# WS2812B.net
KiCad netlist of a schematic drawn in Altium Designer
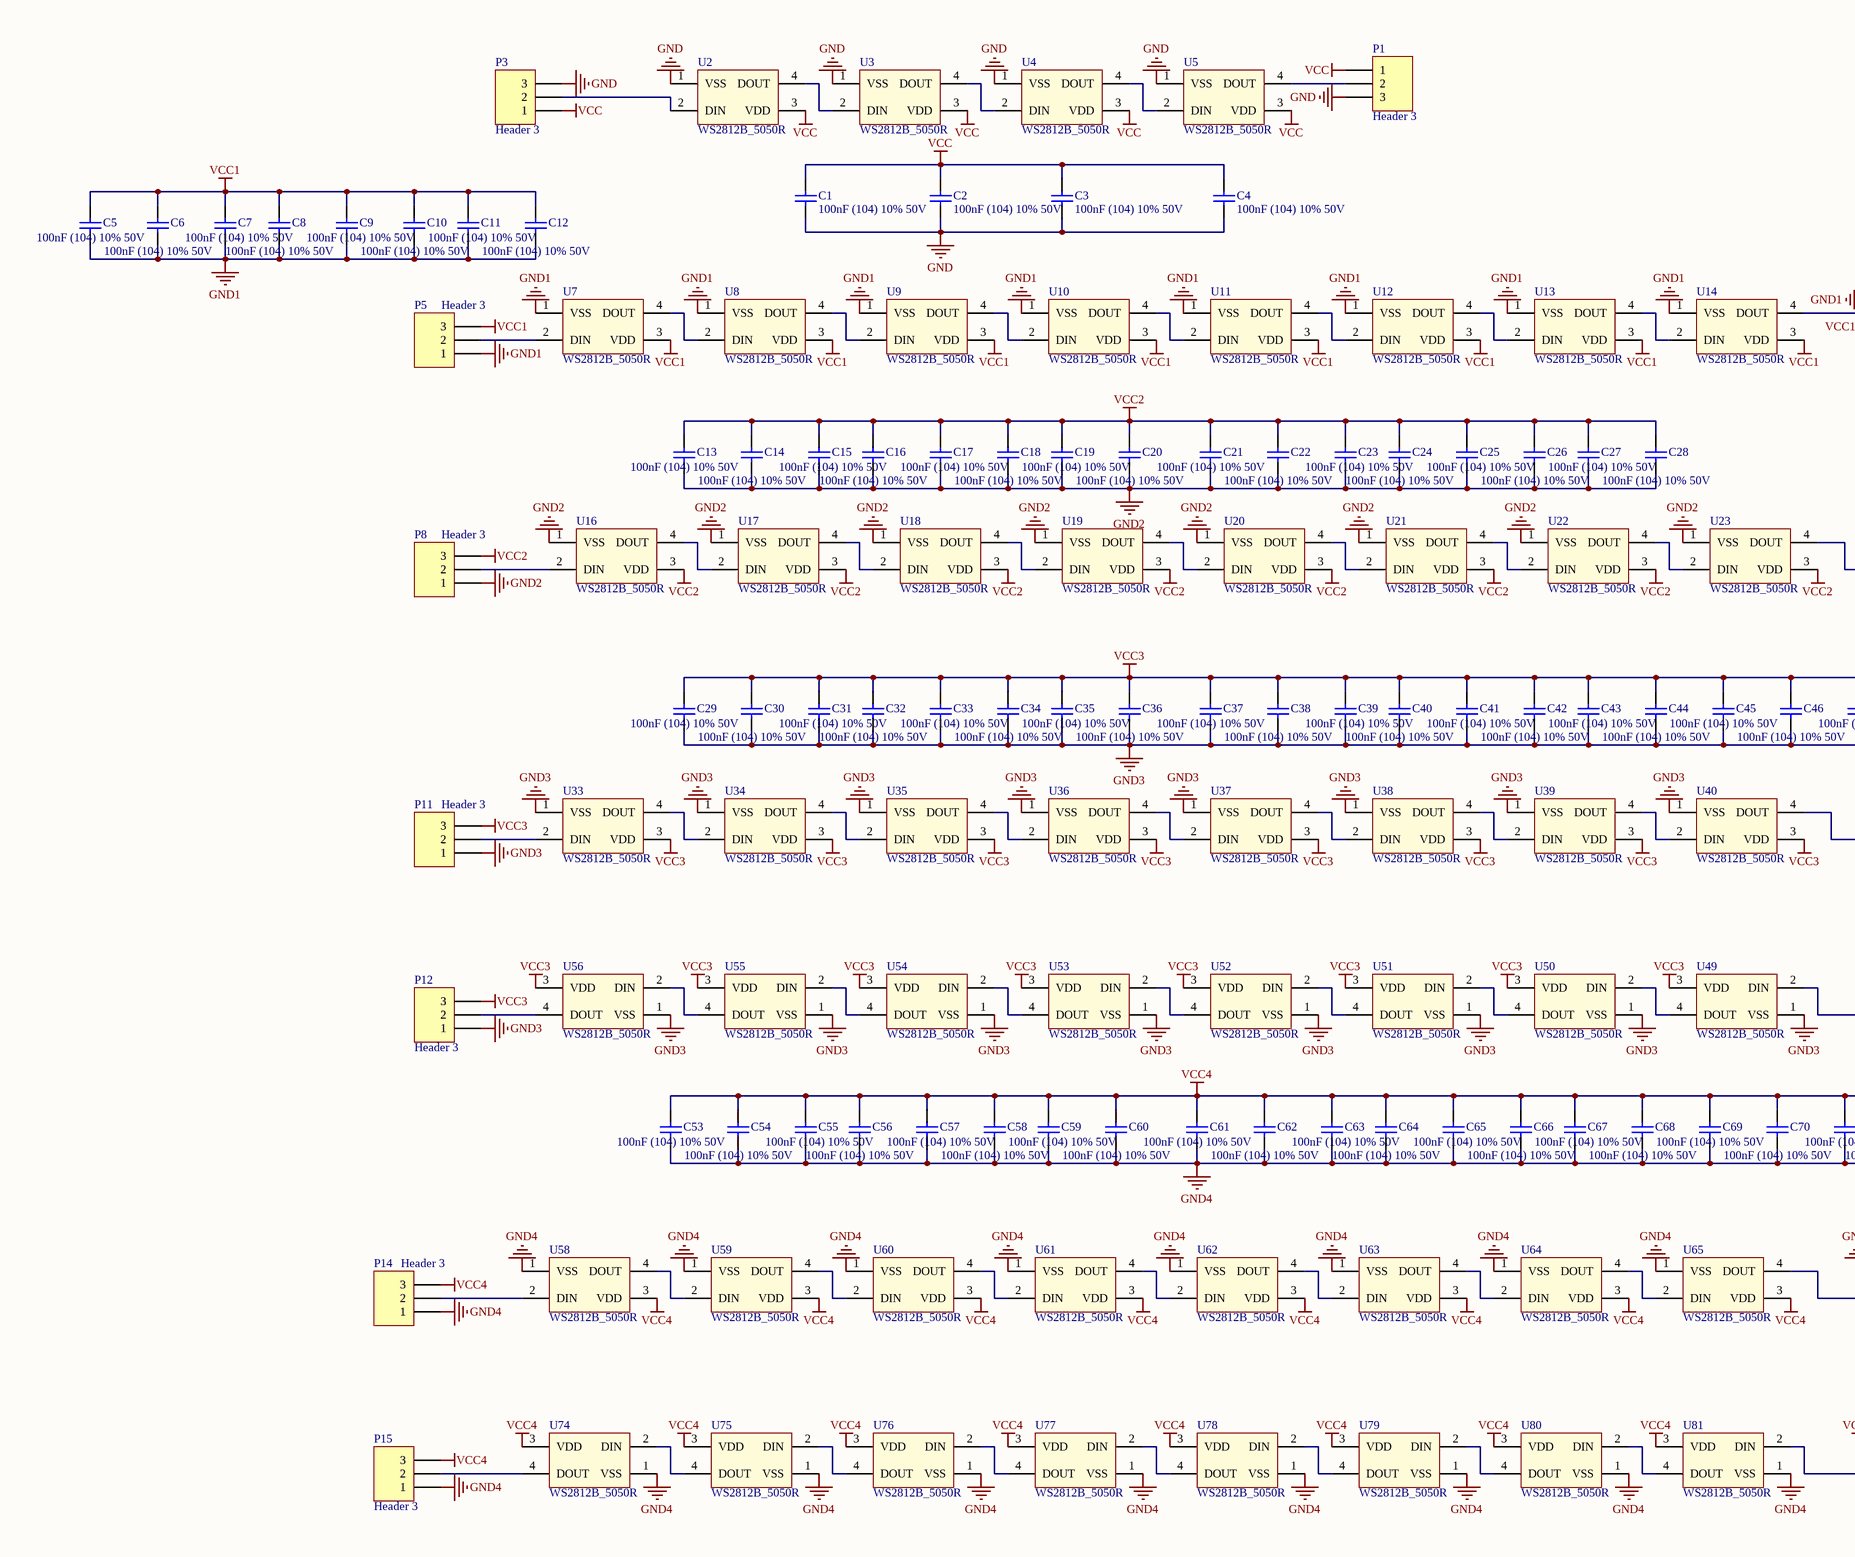
[diagram p0: WS2812B.SchDoc, left]
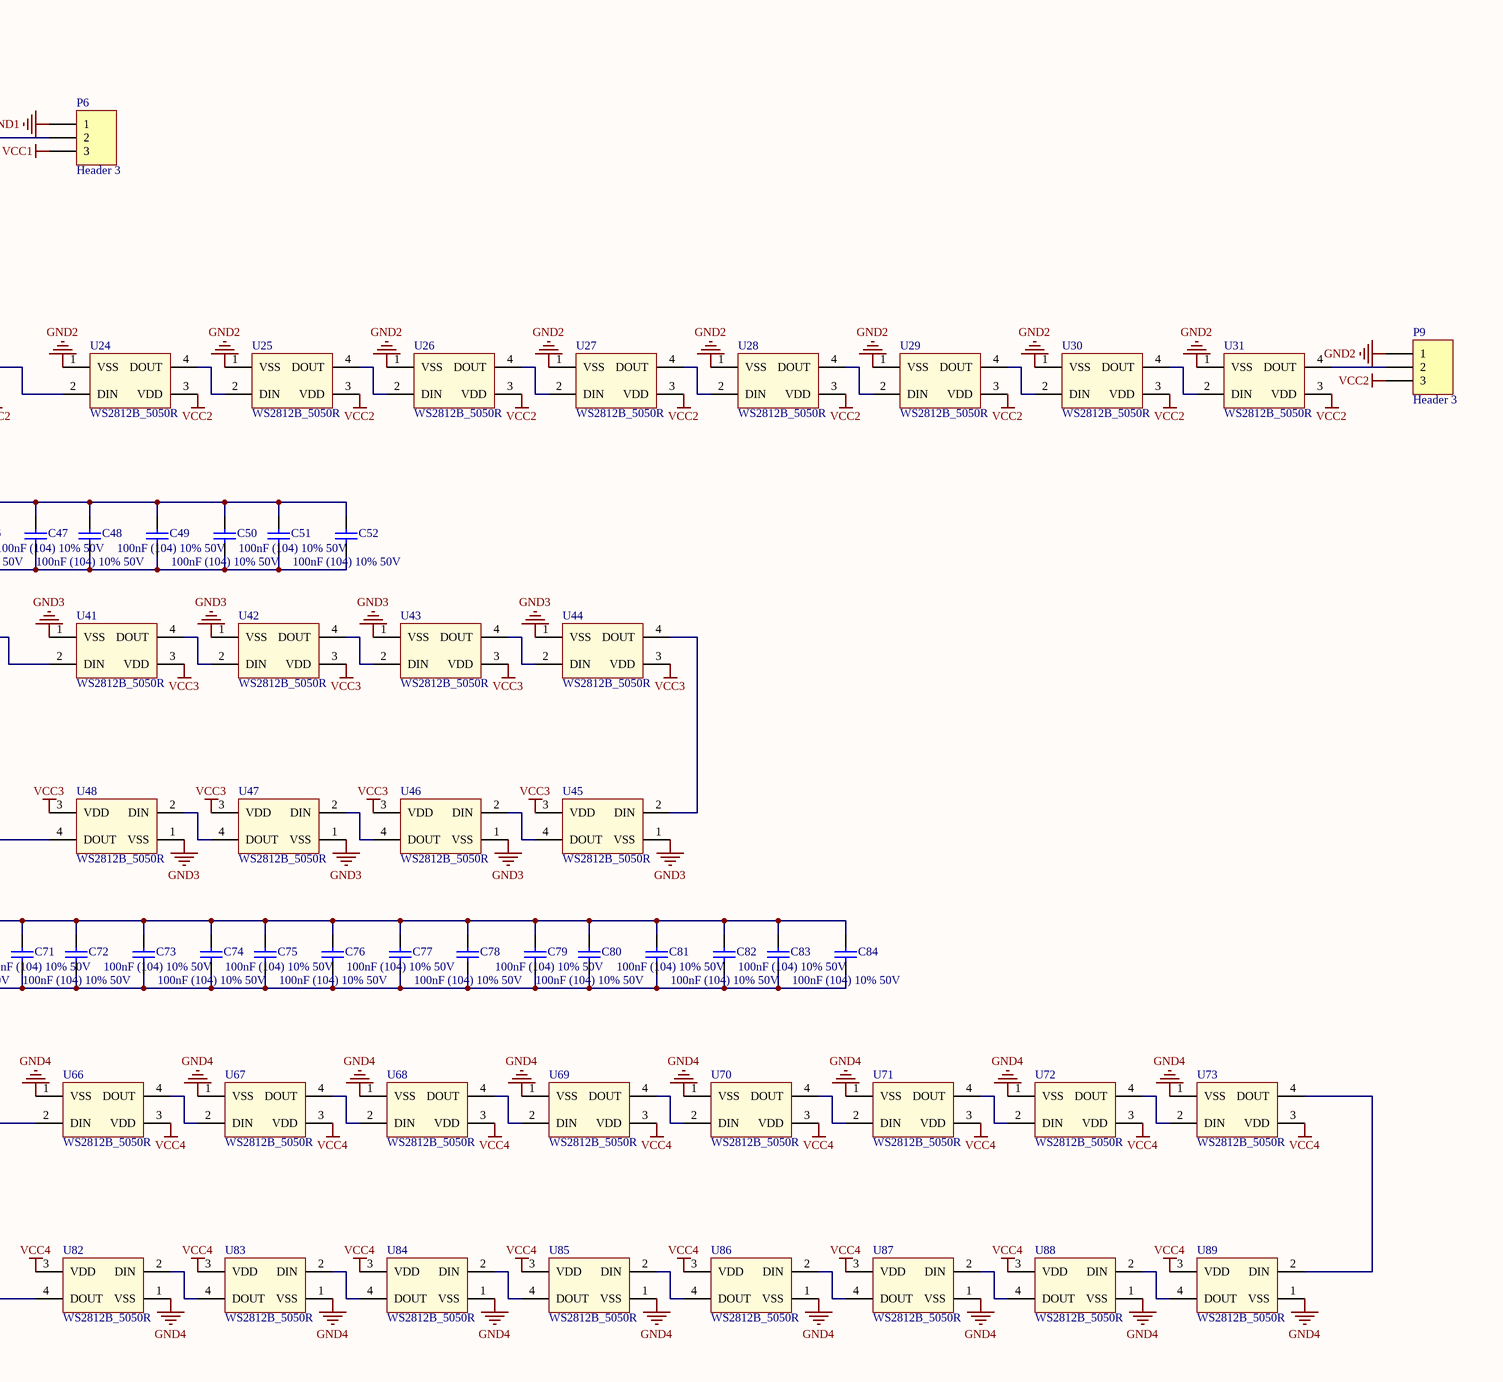
[diagram p1: WS2812B.SchDoc, right]

(export (version "E")
  (design (tool "Eeschema 10.0.6"))
  (components
    (comp (ref "C1")
      (value "100nF (104) 10% 50V")
      (footprint "0603_C")
      (description "贴片电容")
      (libsource (lib "Cap") (part "0603 100nF (104) 10% 50V"))
    )
    (comp (ref "C2")
      (value "100nF (104) 10% 50V")
      (footprint "0603_C")
      (description "贴片电容")
      (libsource (lib "Cap") (part "0603 100nF (104) 10% 50V"))
    )
    (comp (ref "C3")
      (value "100nF (104) 10% 50V")
      (footprint "0603_C")
      (description "贴片电容")
      (libsource (lib "Cap") (part "0603 100nF (104) 10% 50V"))
    )
    (comp (ref "C4")
      (value "100nF (104) 10% 50V")
      (footprint "0603_C")
      (description "贴片电容")
      (libsource (lib "Cap") (part "0603 100nF (104) 10% 50V"))
    )
    (comp (ref "C5")
      (value "100nF (104) 10% 50V")
      (footprint "0603_C")
      (description "贴片电容")
      (libsource (lib "Cap") (part "0603 100nF (104) 10% 50V"))
    )
    (comp (ref "C6")
      (value "100nF (104) 10% 50V")
      (footprint "0603_C")
      (description "贴片电容")
      (libsource (lib "Cap") (part "0603 100nF (104) 10% 50V"))
    )
    (comp (ref "C7")
      (value "100nF (104) 10% 50V")
      (footprint "0603_C")
      (description "贴片电容")
      (libsource (lib "Cap") (part "0603 100nF (104) 10% 50V"))
    )
    (comp (ref "C8")
      (value "100nF (104) 10% 50V")
      (footprint "0603_C")
      (description "贴片电容")
      (libsource (lib "Cap") (part "0603 100nF (104) 10% 50V"))
    )
    (comp (ref "C9")
      (value "100nF (104) 10% 50V")
      (footprint "0603_C")
      (description "贴片电容")
      (libsource (lib "Cap") (part "0603 100nF (104) 10% 50V"))
    )
    (comp (ref "C10")
      (value "100nF (104) 10% 50V")
      (footprint "0603_C")
      (description "贴片电容")
      (libsource (lib "Cap") (part "0603 100nF (104) 10% 50V"))
    )
    (comp (ref "C11")
      (value "100nF (104) 10% 50V")
      (footprint "0603_C")
      (description "贴片电容")
      (libsource (lib "Cap") (part "0603 100nF (104) 10% 50V"))
    )
    (comp (ref "C12")
      (value "100nF (104) 10% 50V")
      (footprint "0603_C")
      (description "贴片电容")
      (libsource (lib "Cap") (part "0603 100nF (104) 10% 50V"))
    )
    (comp (ref "C13")
      (value "100nF (104) 10% 50V")
      (footprint "0603_C")
      (description "贴片电容")
      (libsource (lib "Cap") (part "0603 100nF (104) 10% 50V"))
    )
    (comp (ref "C14")
      (value "100nF (104) 10% 50V")
      (footprint "0603_C")
      (description "贴片电容")
      (libsource (lib "Cap") (part "0603 100nF (104) 10% 50V"))
    )
    (comp (ref "C15")
      (value "100nF (104) 10% 50V")
      (footprint "0603_C")
      (description "贴片电容")
      (libsource (lib "Cap") (part "0603 100nF (104) 10% 50V"))
    )
    (comp (ref "C16")
      (value "100nF (104) 10% 50V")
      (footprint "0603_C")
      (description "贴片电容")
      (libsource (lib "Cap") (part "0603 100nF (104) 10% 50V"))
    )
    (comp (ref "C17")
      (value "100nF (104) 10% 50V")
      (footprint "0603_C")
      (description "贴片电容")
      (libsource (lib "Cap") (part "0603 100nF (104) 10% 50V"))
    )
    (comp (ref "C18")
      (value "100nF (104) 10% 50V")
      (footprint "0603_C")
      (description "贴片电容")
      (libsource (lib "Cap") (part "0603 100nF (104) 10% 50V"))
    )
    (comp (ref "C19")
      (value "100nF (104) 10% 50V")
      (footprint "0603_C")
      (description "贴片电容")
      (libsource (lib "Cap") (part "0603 100nF (104) 10% 50V"))
    )
    (comp (ref "C20")
      (value "100nF (104) 10% 50V")
      (footprint "0603_C")
      (description "贴片电容")
      (libsource (lib "Cap") (part "0603 100nF (104) 10% 50V"))
    )
    (comp (ref "C21")
      (value "100nF (104) 10% 50V")
      (footprint "0603_C")
      (description "贴片电容")
      (libsource (lib "Cap") (part "0603 100nF (104) 10% 50V"))
    )
    (comp (ref "C22")
      (value "100nF (104) 10% 50V")
      (footprint "0603_C")
      (description "贴片电容")
      (libsource (lib "Cap") (part "0603 100nF (104) 10% 50V"))
    )
    (comp (ref "C23")
      (value "100nF (104) 10% 50V")
      (footprint "0603_C")
      (description "贴片电容")
      (libsource (lib "Cap") (part "0603 100nF (104) 10% 50V"))
    )
    (comp (ref "C24")
      (value "100nF (104) 10% 50V")
      (footprint "0603_C")
      (description "贴片电容")
      (libsource (lib "Cap") (part "0603 100nF (104) 10% 50V"))
    )
    (comp (ref "C25")
      (value "100nF (104) 10% 50V")
      (footprint "0603_C")
      (description "贴片电容")
      (libsource (lib "Cap") (part "0603 100nF (104) 10% 50V"))
    )
    (comp (ref "C26")
      (value "100nF (104) 10% 50V")
      (footprint "0603_C")
      (description "贴片电容")
      (libsource (lib "Cap") (part "0603 100nF (104) 10% 50V"))
    )
    (comp (ref "C27")
      (value "100nF (104) 10% 50V")
      (footprint "0603_C")
      (description "贴片电容")
      (libsource (lib "Cap") (part "0603 100nF (104) 10% 50V"))
    )
    (comp (ref "C28")
      (value "100nF (104) 10% 50V")
      (footprint "0603_C")
      (description "贴片电容")
      (libsource (lib "Cap") (part "0603 100nF (104) 10% 50V"))
    )
    (comp (ref "C29")
      (value "100nF (104) 10% 50V")
      (footprint "0603_C")
      (description "贴片电容")
      (libsource (lib "Cap") (part "0603 100nF (104) 10% 50V"))
    )
    (comp (ref "C30")
      (value "100nF (104) 10% 50V")
      (footprint "0603_C")
      (description "贴片电容")
      (libsource (lib "Cap") (part "0603 100nF (104) 10% 50V"))
    )
    (comp (ref "C31")
      (value "100nF (104) 10% 50V")
      (footprint "0603_C")
      (description "贴片电容")
      (libsource (lib "Cap") (part "0603 100nF (104) 10% 50V"))
    )
    (comp (ref "C32")
      (value "100nF (104) 10% 50V")
      (footprint "0603_C")
      (description "贴片电容")
      (libsource (lib "Cap") (part "0603 100nF (104) 10% 50V"))
    )
    (comp (ref "C33")
      (value "100nF (104) 10% 50V")
      (footprint "0603_C")
      (description "贴片电容")
      (libsource (lib "Cap") (part "0603 100nF (104) 10% 50V"))
    )
    (comp (ref "C34")
      (value "100nF (104) 10% 50V")
      (footprint "0603_C")
      (description "贴片电容")
      (libsource (lib "Cap") (part "0603 100nF (104) 10% 50V"))
    )
    (comp (ref "C35")
      (value "100nF (104) 10% 50V")
      (footprint "0603_C")
      (description "贴片电容")
      (libsource (lib "Cap") (part "0603 100nF (104) 10% 50V"))
    )
    (comp (ref "C36")
      (value "100nF (104) 10% 50V")
      (footprint "0603_C")
      (description "贴片电容")
      (libsource (lib "Cap") (part "0603 100nF (104) 10% 50V"))
    )
    (comp (ref "C37")
      (value "100nF (104) 10% 50V")
      (footprint "0603_C")
      (description "贴片电容")
      (libsource (lib "Cap") (part "0603 100nF (104) 10% 50V"))
    )
    (comp (ref "C38")
      (value "100nF (104) 10% 50V")
      (footprint "0603_C")
      (description "贴片电容")
      (libsource (lib "Cap") (part "0603 100nF (104) 10% 50V"))
    )
    (comp (ref "C39")
      (value "100nF (104) 10% 50V")
      (footprint "0603_C")
      (description "贴片电容")
      (libsource (lib "Cap") (part "0603 100nF (104) 10% 50V"))
    )
    (comp (ref "C40")
      (value "100nF (104) 10% 50V")
      (footprint "0603_C")
      (description "贴片电容")
      (libsource (lib "Cap") (part "0603 100nF (104) 10% 50V"))
    )
    (comp (ref "C41")
      (value "100nF (104) 10% 50V")
      (footprint "0603_C")
      (description "贴片电容")
      (libsource (lib "Cap") (part "0603 100nF (104) 10% 50V"))
    )
    (comp (ref "C42")
      (value "100nF (104) 10% 50V")
      (footprint "0603_C")
      (description "贴片电容")
      (libsource (lib "Cap") (part "0603 100nF (104) 10% 50V"))
    )
    (comp (ref "C43")
      (value "100nF (104) 10% 50V")
      (footprint "0603_C")
      (description "贴片电容")
      (libsource (lib "Cap") (part "0603 100nF (104) 10% 50V"))
    )
    (comp (ref "C44")
      (value "100nF (104) 10% 50V")
      (footprint "0603_C")
      (description "贴片电容")
      (libsource (lib "Cap") (part "0603 100nF (104) 10% 50V"))
    )
    (comp (ref "C45")
      (value "100nF (104) 10% 50V")
      (footprint "0603_C")
      (description "贴片电容")
      (libsource (lib "Cap") (part "0603 100nF (104) 10% 50V"))
    )
    (comp (ref "C46")
      (value "100nF (104) 10% 50V")
      (footprint "0603_C")
      (description "贴片电容")
      (libsource (lib "Cap") (part "0603 100nF (104) 10% 50V"))
    )
    (comp (ref "C47")
      (value "100nF (104) 10% 50V")
      (footprint "0603_C")
      (description "贴片电容")
      (libsource (lib "Cap") (part "0603 100nF (104) 10% 50V"))
    )
    (comp (ref "C48")
      (value "100nF (104) 10% 50V")
      (footprint "0603_C")
      (description "贴片电容")
      (libsource (lib "Cap") (part "0603 100nF (104) 10% 50V"))
    )
    (comp (ref "C49")
      (value "100nF (104) 10% 50V")
      (footprint "0603_C")
      (description "贴片电容")
      (libsource (lib "Cap") (part "0603 100nF (104) 10% 50V"))
    )
    (comp (ref "C50")
      (value "100nF (104) 10% 50V")
      (footprint "0603_C")
      (description "贴片电容")
      (libsource (lib "Cap") (part "0603 100nF (104) 10% 50V"))
    )
    (comp (ref "C51")
      (value "100nF (104) 10% 50V")
      (footprint "0603_C")
      (description "贴片电容")
      (libsource (lib "Cap") (part "0603 100nF (104) 10% 50V"))
    )
    (comp (ref "C52")
      (value "100nF (104) 10% 50V")
      (footprint "0603_C")
      (description "贴片电容")
      (libsource (lib "Cap") (part "0603 100nF (104) 10% 50V"))
    )
    (comp (ref "C53")
      (value "100nF (104) 10% 50V")
      (footprint "0603_C")
      (description "贴片电容")
      (libsource (lib "Cap") (part "0603 100nF (104) 10% 50V"))
    )
    (comp (ref "C54")
      (value "100nF (104) 10% 50V")
      (footprint "0603_C")
      (description "贴片电容")
      (libsource (lib "Cap") (part "0603 100nF (104) 10% 50V"))
    )
    (comp (ref "C55")
      (value "100nF (104) 10% 50V")
      (footprint "0603_C")
      (description "贴片电容")
      (libsource (lib "Cap") (part "0603 100nF (104) 10% 50V"))
    )
    (comp (ref "C56")
      (value "100nF (104) 10% 50V")
      (footprint "0603_C")
      (description "贴片电容")
      (libsource (lib "Cap") (part "0603 100nF (104) 10% 50V"))
    )
    (comp (ref "C57")
      (value "100nF (104) 10% 50V")
      (footprint "0603_C")
      (description "贴片电容")
      (libsource (lib "Cap") (part "0603 100nF (104) 10% 50V"))
    )
    (comp (ref "C58")
      (value "100nF (104) 10% 50V")
      (footprint "0603_C")
      (description "贴片电容")
      (libsource (lib "Cap") (part "0603 100nF (104) 10% 50V"))
    )
    (comp (ref "C59")
      (value "100nF (104) 10% 50V")
      (footprint "0603_C")
      (description "贴片电容")
      (libsource (lib "Cap") (part "0603 100nF (104) 10% 50V"))
    )
    (comp (ref "C60")
      (value "100nF (104) 10% 50V")
      (footprint "0603_C")
      (description "贴片电容")
      (libsource (lib "Cap") (part "0603 100nF (104) 10% 50V"))
    )
    (comp (ref "C61")
      (value "100nF (104) 10% 50V")
      (footprint "0603_C")
      (description "贴片电容")
      (libsource (lib "Cap") (part "0603 100nF (104) 10% 50V"))
    )
    (comp (ref "C62")
      (value "100nF (104) 10% 50V")
      (footprint "0603_C")
      (description "贴片电容")
      (libsource (lib "Cap") (part "0603 100nF (104) 10% 50V"))
    )
    (comp (ref "C63")
      (value "100nF (104) 10% 50V")
      (footprint "0603_C")
      (description "贴片电容")
      (libsource (lib "Cap") (part "0603 100nF (104) 10% 50V"))
    )
    (comp (ref "C64")
      (value "100nF (104) 10% 50V")
      (footprint "0603_C")
      (description "贴片电容")
      (libsource (lib "Cap") (part "0603 100nF (104) 10% 50V"))
    )
    (comp (ref "C65")
      (value "100nF (104) 10% 50V")
      (footprint "0603_C")
      (description "贴片电容")
      (libsource (lib "Cap") (part "0603 100nF (104) 10% 50V"))
    )
    (comp (ref "C66")
      (value "100nF (104) 10% 50V")
      (footprint "0603_C")
      (description "贴片电容")
      (libsource (lib "Cap") (part "0603 100nF (104) 10% 50V"))
    )
    (comp (ref "C67")
      (value "100nF (104) 10% 50V")
      (footprint "0603_C")
      (description "贴片电容")
      (libsource (lib "Cap") (part "0603 100nF (104) 10% 50V"))
    )
    (comp (ref "C68")
      (value "100nF (104) 10% 50V")
      (footprint "0603_C")
      (description "贴片电容")
      (libsource (lib "Cap") (part "0603 100nF (104) 10% 50V"))
    )
    (comp (ref "C69")
      (value "100nF (104) 10% 50V")
      (footprint "0603_C")
      (description "贴片电容")
      (libsource (lib "Cap") (part "0603 100nF (104) 10% 50V"))
    )
    (comp (ref "C70")
      (value "100nF (104) 10% 50V")
      (footprint "0603_C")
      (description "贴片电容")
      (libsource (lib "Cap") (part "0603 100nF (104) 10% 50V"))
    )
    (comp (ref "C71")
      (value "100nF (104) 10% 50V")
      (footprint "0603_C")
      (description "贴片电容")
      (libsource (lib "Cap") (part "0603 100nF (104) 10% 50V"))
    )
    (comp (ref "C72")
      (value "100nF (104) 10% 50V")
      (footprint "0603_C")
      (description "贴片电容")
      (libsource (lib "Cap") (part "0603 100nF (104) 10% 50V"))
    )
    (comp (ref "C73")
      (value "100nF (104) 10% 50V")
      (footprint "0603_C")
      (description "贴片电容")
      (libsource (lib "Cap") (part "0603 100nF (104) 10% 50V"))
    )
    (comp (ref "C74")
      (value "100nF (104) 10% 50V")
      (footprint "0603_C")
      (description "贴片电容")
      (libsource (lib "Cap") (part "0603 100nF (104) 10% 50V"))
    )
    (comp (ref "C75")
      (value "100nF (104) 10% 50V")
      (footprint "0603_C")
      (description "贴片电容")
      (libsource (lib "Cap") (part "0603 100nF (104) 10% 50V"))
    )
    (comp (ref "C76")
      (value "100nF (104) 10% 50V")
      (footprint "0603_C")
      (description "贴片电容")
      (libsource (lib "Cap") (part "0603 100nF (104) 10% 50V"))
    )
    (comp (ref "C77")
      (value "100nF (104) 10% 50V")
      (footprint "0603_C")
      (description "贴片电容")
      (libsource (lib "Cap") (part "0603 100nF (104) 10% 50V"))
    )
    (comp (ref "C78")
      (value "100nF (104) 10% 50V")
      (footprint "0603_C")
      (description "贴片电容")
      (libsource (lib "Cap") (part "0603 100nF (104) 10% 50V"))
    )
    (comp (ref "C79")
      (value "100nF (104) 10% 50V")
      (footprint "0603_C")
      (description "贴片电容")
      (libsource (lib "Cap") (part "0603 100nF (104) 10% 50V"))
    )
    (comp (ref "C80")
      (value "100nF (104) 10% 50V")
      (footprint "0603_C")
      (description "贴片电容")
      (libsource (lib "Cap") (part "0603 100nF (104) 10% 50V"))
    )
    (comp (ref "C81")
      (value "100nF (104) 10% 50V")
      (footprint "0603_C")
      (description "贴片电容")
      (libsource (lib "Cap") (part "0603 100nF (104) 10% 50V"))
    )
    (comp (ref "C82")
      (value "100nF (104) 10% 50V")
      (footprint "0603_C")
      (description "贴片电容")
      (libsource (lib "Cap") (part "0603 100nF (104) 10% 50V"))
    )
    (comp (ref "C83")
      (value "100nF (104) 10% 50V")
      (footprint "0603_C")
      (description "贴片电容")
      (libsource (lib "Cap") (part "0603 100nF (104) 10% 50V"))
    )
    (comp (ref "C84")
      (value "100nF (104) 10% 50V")
      (footprint "0603_C")
      (description "贴片电容")
      (libsource (lib "Cap") (part "0603 100nF (104) 10% 50V"))
    )
    (comp (ref "P1")
      (value "Header 3")
      (footprint "PIN3_SMT")
      (description "Header, 3-Pin")
      (fields (field (name "PUBLISHER") "Altium Limited"))
      (libsource (lib "") (part "Header 3_1"))
    )
    (comp (ref "P3")
      (value "Header 3")
      (footprint "PIN3_SMT")
      (description "Header, 3-Pin")
      (fields (field (name "PUBLISHER") "Altium Limited"))
      (libsource (lib "Miscellaneous Connectors") (part "Header 3"))
    )
    (comp (ref "P5")
      (value "Header 3")
      (footprint "PIN3_SMT")
      (description "Header, 3-Pin")
      (fields (field (name "PUBLISHER") "Altium Limited"))
      (libsource (lib "Miscellaneous Connectors") (part "Header 3"))
    )
    (comp (ref "P6")
      (value "Header 3")
      (footprint "PIN3_SMT")
      (description "Header, 3-Pin")
      (fields (field (name "PUBLISHER") "Altium Limited"))
      (libsource (lib "") (part "Header 3_1"))
    )
    (comp (ref "P8")
      (value "Header 3")
      (footprint "PIN3_SMT")
      (description "Header, 3-Pin")
      (fields (field (name "PUBLISHER") "Altium Limited"))
      (libsource (lib "Miscellaneous Connectors") (part "Header 3"))
    )
    (comp (ref "P9")
      (value "Header 3")
      (footprint "PIN3_SMT")
      (description "Header, 3-Pin")
      (fields (field (name "PUBLISHER") "Altium Limited"))
      (libsource (lib "") (part "Header 3_1"))
    )
    (comp (ref "P11")
      (value "Header 3")
      (footprint "PIN3_SMT")
      (description "Header, 3-Pin")
      (fields (field (name "PUBLISHER") "Altium Limited"))
      (libsource (lib "Miscellaneous Connectors") (part "Header 3"))
    )
    (comp (ref "P12")
      (value "Header 3")
      (footprint "PIN3_SMT")
      (description "Header, 3-Pin")
      (fields (field (name "PUBLISHER") "Altium Limited"))
      (libsource (lib "Miscellaneous Connectors") (part "Header 3"))
    )
    (comp (ref "P14")
      (value "Header 3")
      (footprint "PIN3_SMT")
      (description "Header, 3-Pin")
      (fields (field (name "PUBLISHER") "Altium Limited"))
      (libsource (lib "Miscellaneous Connectors") (part "Header 3"))
    )
    (comp (ref "P15")
      (value "Header 3")
      (footprint "PIN3_SMT")
      (description "Header, 3-Pin")
      (fields (field (name "PUBLISHER") "Altium Limited"))
      (libsource (lib "Miscellaneous Connectors") (part "Header 3"))
    )
    (comp (ref "U2")
      (value "WS2812B_5050R")
      (footprint "SW2812B_5050RGB")
      (libsource (lib "") (part "WS2812B_5050RGB_1"))
    )
    (comp (ref "U3")
      (value "WS2812B_5050R")
      (footprint "SW2812B_5050RGB")
      (libsource (lib "") (part "WS2812B_5050RGB_1"))
    )
    (comp (ref "U4")
      (value "WS2812B_5050R")
      (footprint "SW2812B_5050RGB")
      (libsource (lib "") (part "WS2812B_5050RGB_1"))
    )
    (comp (ref "U5")
      (value "WS2812B_5050R")
      (footprint "SW2812B_5050RGB")
      (libsource (lib "") (part "WS2812B_5050RGB_1"))
    )
    (comp (ref "U7")
      (value "WS2812B_5050R")
      (footprint "SW2812B_5050RGB")
      (libsource (lib "") (part "WS2812B_5050RGB_1"))
    )
    (comp (ref "U8")
      (value "WS2812B_5050R")
      (footprint "SW2812B_5050RGB")
      (libsource (lib "") (part "WS2812B_5050RGB_1"))
    )
    (comp (ref "U9")
      (value "WS2812B_5050R")
      (footprint "SW2812B_5050RGB")
      (libsource (lib "") (part "WS2812B_5050RGB_1"))
    )
    (comp (ref "U10")
      (value "WS2812B_5050R")
      (footprint "SW2812B_5050RGB")
      (libsource (lib "") (part "WS2812B_5050RGB_1"))
    )
    (comp (ref "U11")
      (value "WS2812B_5050R")
      (footprint "SW2812B_5050RGB")
      (libsource (lib "") (part "WS2812B_5050RGB_1"))
    )
    (comp (ref "U12")
      (value "WS2812B_5050R")
      (footprint "SW2812B_5050RGB")
      (libsource (lib "") (part "WS2812B_5050RGB_1"))
    )
    (comp (ref "U13")
      (value "WS2812B_5050R")
      (footprint "SW2812B_5050RGB")
      (libsource (lib "") (part "WS2812B_5050RGB_1"))
    )
    (comp (ref "U14")
      (value "WS2812B_5050R")
      (footprint "SW2812B_5050RGB")
      (libsource (lib "") (part "WS2812B_5050RGB_1"))
    )
    (comp (ref "U16")
      (value "WS2812B_5050R")
      (footprint "SW2812B_5050RGB")
      (libsource (lib "") (part "WS2812B_5050RGB_1"))
    )
    (comp (ref "U17")
      (value "WS2812B_5050R")
      (footprint "SW2812B_5050RGB")
      (libsource (lib "") (part "WS2812B_5050RGB_1"))
    )
    (comp (ref "U18")
      (value "WS2812B_5050R")
      (footprint "SW2812B_5050RGB")
      (libsource (lib "") (part "WS2812B_5050RGB_1"))
    )
    (comp (ref "U19")
      (value "WS2812B_5050R")
      (footprint "SW2812B_5050RGB")
      (libsource (lib "") (part "WS2812B_5050RGB_1"))
    )
    (comp (ref "U20")
      (value "WS2812B_5050R")
      (footprint "SW2812B_5050RGB")
      (libsource (lib "") (part "WS2812B_5050RGB_1"))
    )
    (comp (ref "U21")
      (value "WS2812B_5050R")
      (footprint "SW2812B_5050RGB")
      (libsource (lib "") (part "WS2812B_5050RGB_1"))
    )
    (comp (ref "U22")
      (value "WS2812B_5050R")
      (footprint "SW2812B_5050RGB")
      (libsource (lib "") (part "WS2812B_5050RGB_1"))
    )
    (comp (ref "U23")
      (value "WS2812B_5050R")
      (footprint "SW2812B_5050RGB")
      (libsource (lib "") (part "WS2812B_5050RGB_1"))
    )
    (comp (ref "U24")
      (value "WS2812B_5050R")
      (footprint "SW2812B_5050RGB")
      (libsource (lib "") (part "WS2812B_5050RGB_1"))
    )
    (comp (ref "U25")
      (value "WS2812B_5050R")
      (footprint "SW2812B_5050RGB")
      (libsource (lib "") (part "WS2812B_5050RGB_1"))
    )
    (comp (ref "U26")
      (value "WS2812B_5050R")
      (footprint "SW2812B_5050RGB")
      (libsource (lib "") (part "WS2812B_5050RGB_1"))
    )
    (comp (ref "U27")
      (value "WS2812B_5050R")
      (footprint "SW2812B_5050RGB")
      (libsource (lib "") (part "WS2812B_5050RGB_1"))
    )
    (comp (ref "U28")
      (value "WS2812B_5050R")
      (footprint "SW2812B_5050RGB")
      (libsource (lib "") (part "WS2812B_5050RGB_1"))
    )
    (comp (ref "U29")
      (value "WS2812B_5050R")
      (footprint "SW2812B_5050RGB")
      (libsource (lib "") (part "WS2812B_5050RGB_1"))
    )
    (comp (ref "U30")
      (value "WS2812B_5050R")
      (footprint "SW2812B_5050RGB")
      (libsource (lib "") (part "WS2812B_5050RGB_1"))
    )
    (comp (ref "U31")
      (value "WS2812B_5050R")
      (footprint "SW2812B_5050RGB")
      (libsource (lib "") (part "WS2812B_5050RGB_1"))
    )
    (comp (ref "U33")
      (value "WS2812B_5050R")
      (footprint "SW2812B_5050RGB")
      (libsource (lib "") (part "WS2812B_5050RGB_1"))
    )
    (comp (ref "U34")
      (value "WS2812B_5050R")
      (footprint "SW2812B_5050RGB")
      (libsource (lib "") (part "WS2812B_5050RGB_1"))
    )
    (comp (ref "U35")
      (value "WS2812B_5050R")
      (footprint "SW2812B_5050RGB")
      (libsource (lib "") (part "WS2812B_5050RGB_1"))
    )
    (comp (ref "U36")
      (value "WS2812B_5050R")
      (footprint "SW2812B_5050RGB")
      (libsource (lib "") (part "WS2812B_5050RGB_1"))
    )
    (comp (ref "U37")
      (value "WS2812B_5050R")
      (footprint "SW2812B_5050RGB")
      (libsource (lib "") (part "WS2812B_5050RGB_1"))
    )
    (comp (ref "U38")
      (value "WS2812B_5050R")
      (footprint "SW2812B_5050RGB")
      (libsource (lib "") (part "WS2812B_5050RGB_1"))
    )
    (comp (ref "U39")
      (value "WS2812B_5050R")
      (footprint "SW2812B_5050RGB")
      (libsource (lib "") (part "WS2812B_5050RGB_1"))
    )
    (comp (ref "U40")
      (value "WS2812B_5050R")
      (footprint "SW2812B_5050RGB")
      (libsource (lib "") (part "WS2812B_5050RGB_1"))
    )
    (comp (ref "U41")
      (value "WS2812B_5050R")
      (footprint "SW2812B_5050RGB")
      (libsource (lib "") (part "WS2812B_5050RGB_1"))
    )
    (comp (ref "U42")
      (value "WS2812B_5050R")
      (footprint "SW2812B_5050RGB")
      (libsource (lib "") (part "WS2812B_5050RGB_1"))
    )
    (comp (ref "U43")
      (value "WS2812B_5050R")
      (footprint "SW2812B_5050RGB")
      (libsource (lib "") (part "WS2812B_5050RGB_1"))
    )
    (comp (ref "U44")
      (value "WS2812B_5050R")
      (footprint "SW2812B_5050RGB")
      (libsource (lib "") (part "WS2812B_5050RGB_1"))
    )
    (comp (ref "U45")
      (value "WS2812B_5050R")
      (footprint "SW2812B_5050RGB")
      (libsource (lib "mylib") (part "WS2812B_5050RGB"))
    )
    (comp (ref "U46")
      (value "WS2812B_5050R")
      (footprint "SW2812B_5050RGB")
      (libsource (lib "mylib") (part "WS2812B_5050RGB"))
    )
    (comp (ref "U47")
      (value "WS2812B_5050R")
      (footprint "SW2812B_5050RGB")
      (libsource (lib "mylib") (part "WS2812B_5050RGB"))
    )
    (comp (ref "U48")
      (value "WS2812B_5050R")
      (footprint "SW2812B_5050RGB")
      (libsource (lib "mylib") (part "WS2812B_5050RGB"))
    )
    (comp (ref "U49")
      (value "WS2812B_5050R")
      (footprint "SW2812B_5050RGB")
      (libsource (lib "mylib") (part "WS2812B_5050RGB"))
    )
    (comp (ref "U50")
      (value "WS2812B_5050R")
      (footprint "SW2812B_5050RGB")
      (libsource (lib "mylib") (part "WS2812B_5050RGB"))
    )
    (comp (ref "U51")
      (value "WS2812B_5050R")
      (footprint "SW2812B_5050RGB")
      (libsource (lib "mylib") (part "WS2812B_5050RGB"))
    )
    (comp (ref "U52")
      (value "WS2812B_5050R")
      (footprint "SW2812B_5050RGB")
      (libsource (lib "mylib") (part "WS2812B_5050RGB"))
    )
    (comp (ref "U53")
      (value "WS2812B_5050R")
      (footprint "SW2812B_5050RGB")
      (libsource (lib "mylib") (part "WS2812B_5050RGB"))
    )
    (comp (ref "U54")
      (value "WS2812B_5050R")
      (footprint "SW2812B_5050RGB")
      (libsource (lib "mylib") (part "WS2812B_5050RGB"))
    )
    (comp (ref "U55")
      (value "WS2812B_5050R")
      (footprint "SW2812B_5050RGB")
      (libsource (lib "mylib") (part "WS2812B_5050RGB"))
    )
    (comp (ref "U56")
      (value "WS2812B_5050R")
      (footprint "SW2812B_5050RGB")
      (libsource (lib "mylib") (part "WS2812B_5050RGB"))
    )
    (comp (ref "U58")
      (value "WS2812B_5050R")
      (footprint "SW2812B_5050RGB")
      (libsource (lib "") (part "WS2812B_5050RGB_1"))
    )
    (comp (ref "U59")
      (value "WS2812B_5050R")
      (footprint "SW2812B_5050RGB")
      (libsource (lib "") (part "WS2812B_5050RGB_1"))
    )
    (comp (ref "U60")
      (value "WS2812B_5050R")
      (footprint "SW2812B_5050RGB")
      (libsource (lib "") (part "WS2812B_5050RGB_1"))
    )
    (comp (ref "U61")
      (value "WS2812B_5050R")
      (footprint "SW2812B_5050RGB")
      (libsource (lib "") (part "WS2812B_5050RGB_1"))
    )
    (comp (ref "U62")
      (value "WS2812B_5050R")
      (footprint "SW2812B_5050RGB")
      (libsource (lib "") (part "WS2812B_5050RGB_1"))
    )
    (comp (ref "U63")
      (value "WS2812B_5050R")
      (footprint "SW2812B_5050RGB")
      (libsource (lib "") (part "WS2812B_5050RGB_1"))
    )
    (comp (ref "U64")
      (value "WS2812B_5050R")
      (footprint "SW2812B_5050RGB")
      (libsource (lib "") (part "WS2812B_5050RGB_1"))
    )
    (comp (ref "U65")
      (value "WS2812B_5050R")
      (footprint "SW2812B_5050RGB")
      (libsource (lib "") (part "WS2812B_5050RGB_1"))
    )
    (comp (ref "U66")
      (value "WS2812B_5050R")
      (footprint "SW2812B_5050RGB")
      (libsource (lib "") (part "WS2812B_5050RGB_1"))
    )
    (comp (ref "U67")
      (value "WS2812B_5050R")
      (footprint "SW2812B_5050RGB")
      (libsource (lib "") (part "WS2812B_5050RGB_1"))
    )
    (comp (ref "U68")
      (value "WS2812B_5050R")
      (footprint "SW2812B_5050RGB")
      (libsource (lib "") (part "WS2812B_5050RGB_1"))
    )
    (comp (ref "U69")
      (value "WS2812B_5050R")
      (footprint "SW2812B_5050RGB")
      (libsource (lib "") (part "WS2812B_5050RGB_1"))
    )
    (comp (ref "U70")
      (value "WS2812B_5050R")
      (footprint "SW2812B_5050RGB")
      (libsource (lib "") (part "WS2812B_5050RGB_1"))
    )
    (comp (ref "U71")
      (value "WS2812B_5050R")
      (footprint "SW2812B_5050RGB")
      (libsource (lib "") (part "WS2812B_5050RGB_1"))
    )
    (comp (ref "U72")
      (value "WS2812B_5050R")
      (footprint "SW2812B_5050RGB")
      (libsource (lib "") (part "WS2812B_5050RGB_1"))
    )
    (comp (ref "U73")
      (value "WS2812B_5050R")
      (footprint "SW2812B_5050RGB")
      (libsource (lib "") (part "WS2812B_5050RGB_1"))
    )
    (comp (ref "U74")
      (value "WS2812B_5050R")
      (footprint "SW2812B_5050RGB")
      (libsource (lib "mylib") (part "WS2812B_5050RGB"))
    )
    (comp (ref "U75")
      (value "WS2812B_5050R")
      (footprint "SW2812B_5050RGB")
      (libsource (lib "mylib") (part "WS2812B_5050RGB"))
    )
    (comp (ref "U76")
      (value "WS2812B_5050R")
      (footprint "SW2812B_5050RGB")
      (libsource (lib "mylib") (part "WS2812B_5050RGB"))
    )
    (comp (ref "U77")
      (value "WS2812B_5050R")
      (footprint "SW2812B_5050RGB")
      (libsource (lib "mylib") (part "WS2812B_5050RGB"))
    )
    (comp (ref "U78")
      (value "WS2812B_5050R")
      (footprint "SW2812B_5050RGB")
      (libsource (lib "mylib") (part "WS2812B_5050RGB"))
    )
    (comp (ref "U79")
      (value "WS2812B_5050R")
      (footprint "SW2812B_5050RGB")
      (libsource (lib "mylib") (part "WS2812B_5050RGB"))
    )
    (comp (ref "U80")
      (value "WS2812B_5050R")
      (footprint "SW2812B_5050RGB")
      (libsource (lib "mylib") (part "WS2812B_5050RGB"))
    )
    (comp (ref "U81")
      (value "WS2812B_5050R")
      (footprint "SW2812B_5050RGB")
      (libsource (lib "mylib") (part "WS2812B_5050RGB"))
    )
    (comp (ref "U82")
      (value "WS2812B_5050R")
      (footprint "SW2812B_5050RGB")
      (libsource (lib "mylib") (part "WS2812B_5050RGB"))
    )
    (comp (ref "U83")
      (value "WS2812B_5050R")
      (footprint "SW2812B_5050RGB")
      (libsource (lib "mylib") (part "WS2812B_5050RGB"))
    )
    (comp (ref "U84")
      (value "WS2812B_5050R")
      (footprint "SW2812B_5050RGB")
      (libsource (lib "mylib") (part "WS2812B_5050RGB"))
    )
    (comp (ref "U85")
      (value "WS2812B_5050R")
      (footprint "SW2812B_5050RGB")
      (libsource (lib "mylib") (part "WS2812B_5050RGB"))
    )
    (comp (ref "U86")
      (value "WS2812B_5050R")
      (footprint "SW2812B_5050RGB")
      (libsource (lib "mylib") (part "WS2812B_5050RGB"))
    )
    (comp (ref "U87")
      (value "WS2812B_5050R")
      (footprint "SW2812B_5050RGB")
      (libsource (lib "mylib") (part "WS2812B_5050RGB"))
    )
    (comp (ref "U88")
      (value "WS2812B_5050R")
      (footprint "SW2812B_5050RGB")
      (libsource (lib "mylib") (part "WS2812B_5050RGB"))
    )
    (comp (ref "U89")
      (value "WS2812B_5050R")
      (footprint "SW2812B_5050RGB")
      (libsource (lib "mylib") (part "WS2812B_5050RGB"))
    )
  )
  (nets
    (net (code "1") (name "GND") (class "Default")
      (node (ref "C1") (pin "1") (pinfunction "1_1") (pintype "passive"))
      (node (ref "C2") (pin "1") (pinfunction "1_1") (pintype "passive"))
      (node (ref "C3") (pin "1") (pinfunction "1_1") (pintype "passive"))
      (node (ref "C4") (pin "1") (pinfunction "1_1") (pintype "passive"))
      (node (ref "P1") (pin "3") (pinfunction "3_3") (pintype "passive"))
      (node (ref "P3") (pin "3") (pinfunction "3_3") (pintype "passive"))
      (node (ref "U2") (pin "1") (pinfunction "VSS_1") (pintype "passive"))
      (node (ref "U3") (pin "1") (pinfunction "VSS_1") (pintype "passive"))
      (node (ref "U4") (pin "1") (pinfunction "VSS_1") (pintype "passive"))
      (node (ref "U5") (pin "1") (pinfunction "VSS_1") (pintype "passive"))
    )
    (net (code "2") (name "GND1") (class "Default")
      (node (ref "C10") (pin "1") (pinfunction "1_1") (pintype "passive"))
      (node (ref "C11") (pin "1") (pinfunction "1_1") (pintype "passive"))
      (node (ref "C12") (pin "1") (pinfunction "1_1") (pintype "passive"))
      (node (ref "C5") (pin "1") (pinfunction "1_1") (pintype "passive"))
      (node (ref "C6") (pin "1") (pinfunction "1_1") (pintype "passive"))
      (node (ref "C7") (pin "1") (pinfunction "1_1") (pintype "passive"))
      (node (ref "C8") (pin "1") (pinfunction "1_1") (pintype "passive"))
      (node (ref "C9") (pin "1") (pinfunction "1_1") (pintype "passive"))
      (node (ref "P5") (pin "1") (pinfunction "1_1") (pintype "passive"))
      (node (ref "P6") (pin "1") (pinfunction "1_1") (pintype "passive"))
      (node (ref "U10") (pin "1") (pinfunction "VSS_1") (pintype "passive"))
      (node (ref "U11") (pin "1") (pinfunction "VSS_1") (pintype "passive"))
      (node (ref "U12") (pin "1") (pinfunction "VSS_1") (pintype "passive"))
      (node (ref "U13") (pin "1") (pinfunction "VSS_1") (pintype "passive"))
      (node (ref "U14") (pin "1") (pinfunction "VSS_1") (pintype "passive"))
      (node (ref "U7") (pin "1") (pinfunction "VSS_1") (pintype "passive"))
      (node (ref "U8") (pin "1") (pinfunction "VSS_1") (pintype "passive"))
      (node (ref "U9") (pin "1") (pinfunction "VSS_1") (pintype "passive"))
    )
    (net (code "3") (name "GND2") (class "Default")
      (node (ref "C13") (pin "1") (pinfunction "1_1") (pintype "passive"))
      (node (ref "C14") (pin "1") (pinfunction "1_1") (pintype "passive"))
      (node (ref "C15") (pin "1") (pinfunction "1_1") (pintype "passive"))
      (node (ref "C16") (pin "1") (pinfunction "1_1") (pintype "passive"))
      (node (ref "C17") (pin "1") (pinfunction "1_1") (pintype "passive"))
      (node (ref "C18") (pin "1") (pinfunction "1_1") (pintype "passive"))
      (node (ref "C19") (pin "1") (pinfunction "1_1") (pintype "passive"))
      (node (ref "C20") (pin "1") (pinfunction "1_1") (pintype "passive"))
      (node (ref "C21") (pin "1") (pinfunction "1_1") (pintype "passive"))
      (node (ref "C22") (pin "1") (pinfunction "1_1") (pintype "passive"))
      (node (ref "C23") (pin "1") (pinfunction "1_1") (pintype "passive"))
      (node (ref "C24") (pin "1") (pinfunction "1_1") (pintype "passive"))
      (node (ref "C25") (pin "1") (pinfunction "1_1") (pintype "passive"))
      (node (ref "C26") (pin "1") (pinfunction "1_1") (pintype "passive"))
      (node (ref "C27") (pin "1") (pinfunction "1_1") (pintype "passive"))
      (node (ref "C28") (pin "1") (pinfunction "1_1") (pintype "passive"))
      (node (ref "P8") (pin "1") (pinfunction "1_1") (pintype "passive"))
      (node (ref "P9") (pin "1") (pinfunction "1_1") (pintype "passive"))
      (node (ref "U16") (pin "1") (pinfunction "VSS_1") (pintype "passive"))
      (node (ref "U17") (pin "1") (pinfunction "VSS_1") (pintype "passive"))
      (node (ref "U18") (pin "1") (pinfunction "VSS_1") (pintype "passive"))
      (node (ref "U19") (pin "1") (pinfunction "VSS_1") (pintype "passive"))
      (node (ref "U20") (pin "1") (pinfunction "VSS_1") (pintype "passive"))
      (node (ref "U21") (pin "1") (pinfunction "VSS_1") (pintype "passive"))
      (node (ref "U22") (pin "1") (pinfunction "VSS_1") (pintype "passive"))
      (node (ref "U23") (pin "1") (pinfunction "VSS_1") (pintype "passive"))
      (node (ref "U24") (pin "1") (pinfunction "VSS_1") (pintype "passive"))
      (node (ref "U25") (pin "1") (pinfunction "VSS_1") (pintype "passive"))
      (node (ref "U26") (pin "1") (pinfunction "VSS_1") (pintype "passive"))
      (node (ref "U27") (pin "1") (pinfunction "VSS_1") (pintype "passive"))
      (node (ref "U28") (pin "1") (pinfunction "VSS_1") (pintype "passive"))
      (node (ref "U29") (pin "1") (pinfunction "VSS_1") (pintype "passive"))
      (node (ref "U30") (pin "1") (pinfunction "VSS_1") (pintype "passive"))
      (node (ref "U31") (pin "1") (pinfunction "VSS_1") (pintype "passive"))
    )
    (net (code "4") (name "GND3") (class "Default")
      (node (ref "C29") (pin "1") (pinfunction "1_1") (pintype "passive"))
      (node (ref "C30") (pin "1") (pinfunction "1_1") (pintype "passive"))
      (node (ref "C31") (pin "1") (pinfunction "1_1") (pintype "passive"))
      (node (ref "C32") (pin "1") (pinfunction "1_1") (pintype "passive"))
      (node (ref "C33") (pin "1") (pinfunction "1_1") (pintype "passive"))
      (node (ref "C34") (pin "1") (pinfunction "1_1") (pintype "passive"))
      (node (ref "C35") (pin "1") (pinfunction "1_1") (pintype "passive"))
      (node (ref "C36") (pin "1") (pinfunction "1_1") (pintype "passive"))
      (node (ref "C37") (pin "1") (pinfunction "1_1") (pintype "passive"))
      (node (ref "C38") (pin "1") (pinfunction "1_1") (pintype "passive"))
      (node (ref "C39") (pin "1") (pinfunction "1_1") (pintype "passive"))
      (node (ref "C40") (pin "1") (pinfunction "1_1") (pintype "passive"))
      (node (ref "C41") (pin "1") (pinfunction "1_1") (pintype "passive"))
      (node (ref "C42") (pin "1") (pinfunction "1_1") (pintype "passive"))
      (node (ref "C43") (pin "1") (pinfunction "1_1") (pintype "passive"))
      (node (ref "C44") (pin "1") (pinfunction "1_1") (pintype "passive"))
      (node (ref "C45") (pin "1") (pinfunction "1_1") (pintype "passive"))
      (node (ref "C46") (pin "1") (pinfunction "1_1") (pintype "passive"))
      (node (ref "C47") (pin "1") (pinfunction "1_1") (pintype "passive"))
      (node (ref "C48") (pin "1") (pinfunction "1_1") (pintype "passive"))
      (node (ref "C49") (pin "1") (pinfunction "1_1") (pintype "passive"))
      (node (ref "C50") (pin "1") (pinfunction "1_1") (pintype "passive"))
      (node (ref "C51") (pin "1") (pinfunction "1_1") (pintype "passive"))
      (node (ref "C52") (pin "1") (pinfunction "1_1") (pintype "passive"))
      (node (ref "P11") (pin "1") (pinfunction "1_1") (pintype "passive"))
      (node (ref "P12") (pin "1") (pinfunction "1_1") (pintype "passive"))
      (node (ref "U33") (pin "1") (pinfunction "VSS_1") (pintype "passive"))
      (node (ref "U34") (pin "1") (pinfunction "VSS_1") (pintype "passive"))
      (node (ref "U35") (pin "1") (pinfunction "VSS_1") (pintype "passive"))
      (node (ref "U36") (pin "1") (pinfunction "VSS_1") (pintype "passive"))
      (node (ref "U37") (pin "1") (pinfunction "VSS_1") (pintype "passive"))
      (node (ref "U38") (pin "1") (pinfunction "VSS_1") (pintype "passive"))
      (node (ref "U39") (pin "1") (pinfunction "VSS_1") (pintype "passive"))
      (node (ref "U40") (pin "1") (pinfunction "VSS_1") (pintype "passive"))
      (node (ref "U41") (pin "1") (pinfunction "VSS_1") (pintype "passive"))
      (node (ref "U42") (pin "1") (pinfunction "VSS_1") (pintype "passive"))
      (node (ref "U43") (pin "1") (pinfunction "VSS_1") (pintype "passive"))
      (node (ref "U44") (pin "1") (pinfunction "VSS_1") (pintype "passive"))
      (node (ref "U45") (pin "1") (pinfunction "VSS_1") (pintype "passive"))
      (node (ref "U46") (pin "1") (pinfunction "VSS_1") (pintype "passive"))
      (node (ref "U47") (pin "1") (pinfunction "VSS_1") (pintype "passive"))
      (node (ref "U48") (pin "1") (pinfunction "VSS_1") (pintype "passive"))
      (node (ref "U49") (pin "1") (pinfunction "VSS_1") (pintype "passive"))
      (node (ref "U50") (pin "1") (pinfunction "VSS_1") (pintype "passive"))
      (node (ref "U51") (pin "1") (pinfunction "VSS_1") (pintype "passive"))
      (node (ref "U52") (pin "1") (pinfunction "VSS_1") (pintype "passive"))
      (node (ref "U53") (pin "1") (pinfunction "VSS_1") (pintype "passive"))
      (node (ref "U54") (pin "1") (pinfunction "VSS_1") (pintype "passive"))
      (node (ref "U55") (pin "1") (pinfunction "VSS_1") (pintype "passive"))
      (node (ref "U56") (pin "1") (pinfunction "VSS_1") (pintype "passive"))
    )
    (net (code "5") (name "GND4") (class "Default")
      (node (ref "C53") (pin "1") (pinfunction "1_1") (pintype "passive"))
      (node (ref "C54") (pin "1") (pinfunction "1_1") (pintype "passive"))
      (node (ref "C55") (pin "1") (pinfunction "1_1") (pintype "passive"))
      (node (ref "C56") (pin "1") (pinfunction "1_1") (pintype "passive"))
      (node (ref "C57") (pin "1") (pinfunction "1_1") (pintype "passive"))
      (node (ref "C58") (pin "1") (pinfunction "1_1") (pintype "passive"))
      (node (ref "C59") (pin "1") (pinfunction "1_1") (pintype "passive"))
      (node (ref "C60") (pin "1") (pinfunction "1_1") (pintype "passive"))
      (node (ref "C61") (pin "1") (pinfunction "1_1") (pintype "passive"))
      (node (ref "C62") (pin "1") (pinfunction "1_1") (pintype "passive"))
      (node (ref "C63") (pin "1") (pinfunction "1_1") (pintype "passive"))
      (node (ref "C64") (pin "1") (pinfunction "1_1") (pintype "passive"))
      (node (ref "C65") (pin "1") (pinfunction "1_1") (pintype "passive"))
      (node (ref "C66") (pin "1") (pinfunction "1_1") (pintype "passive"))
      (node (ref "C67") (pin "1") (pinfunction "1_1") (pintype "passive"))
      (node (ref "C68") (pin "1") (pinfunction "1_1") (pintype "passive"))
      (node (ref "C69") (pin "1") (pinfunction "1_1") (pintype "passive"))
      (node (ref "C70") (pin "1") (pinfunction "1_1") (pintype "passive"))
      (node (ref "C71") (pin "1") (pinfunction "1_1") (pintype "passive"))
      (node (ref "C72") (pin "1") (pinfunction "1_1") (pintype "passive"))
      (node (ref "C73") (pin "1") (pinfunction "1_1") (pintype "passive"))
      (node (ref "C74") (pin "1") (pinfunction "1_1") (pintype "passive"))
      (node (ref "C75") (pin "1") (pinfunction "1_1") (pintype "passive"))
      (node (ref "C76") (pin "1") (pinfunction "1_1") (pintype "passive"))
      (node (ref "C77") (pin "1") (pinfunction "1_1") (pintype "passive"))
      (node (ref "C78") (pin "1") (pinfunction "1_1") (pintype "passive"))
      (node (ref "C79") (pin "1") (pinfunction "1_1") (pintype "passive"))
      (node (ref "C80") (pin "1") (pinfunction "1_1") (pintype "passive"))
      (node (ref "C81") (pin "1") (pinfunction "1_1") (pintype "passive"))
      (node (ref "C82") (pin "1") (pinfunction "1_1") (pintype "passive"))
      (node (ref "C83") (pin "1") (pinfunction "1_1") (pintype "passive"))
      (node (ref "C84") (pin "1") (pinfunction "1_1") (pintype "passive"))
      (node (ref "P14") (pin "1") (pinfunction "1_1") (pintype "passive"))
      (node (ref "P15") (pin "1") (pinfunction "1_1") (pintype "passive"))
      (node (ref "U58") (pin "1") (pinfunction "VSS_1") (pintype "passive"))
      (node (ref "U59") (pin "1") (pinfunction "VSS_1") (pintype "passive"))
      (node (ref "U60") (pin "1") (pinfunction "VSS_1") (pintype "passive"))
      (node (ref "U61") (pin "1") (pinfunction "VSS_1") (pintype "passive"))
      (node (ref "U62") (pin "1") (pinfunction "VSS_1") (pintype "passive"))
      (node (ref "U63") (pin "1") (pinfunction "VSS_1") (pintype "passive"))
      (node (ref "U64") (pin "1") (pinfunction "VSS_1") (pintype "passive"))
      (node (ref "U65") (pin "1") (pinfunction "VSS_1") (pintype "passive"))
      (node (ref "U66") (pin "1") (pinfunction "VSS_1") (pintype "passive"))
      (node (ref "U67") (pin "1") (pinfunction "VSS_1") (pintype "passive"))
      (node (ref "U68") (pin "1") (pinfunction "VSS_1") (pintype "passive"))
      (node (ref "U69") (pin "1") (pinfunction "VSS_1") (pintype "passive"))
      (node (ref "U70") (pin "1") (pinfunction "VSS_1") (pintype "passive"))
      (node (ref "U71") (pin "1") (pinfunction "VSS_1") (pintype "passive"))
      (node (ref "U72") (pin "1") (pinfunction "VSS_1") (pintype "passive"))
      (node (ref "U73") (pin "1") (pinfunction "VSS_1") (pintype "passive"))
      (node (ref "U74") (pin "1") (pinfunction "VSS_1") (pintype "passive"))
      (node (ref "U75") (pin "1") (pinfunction "VSS_1") (pintype "passive"))
      (node (ref "U76") (pin "1") (pinfunction "VSS_1") (pintype "passive"))
      (node (ref "U77") (pin "1") (pinfunction "VSS_1") (pintype "passive"))
      (node (ref "U78") (pin "1") (pinfunction "VSS_1") (pintype "passive"))
      (node (ref "U79") (pin "1") (pinfunction "VSS_1") (pintype "passive"))
      (node (ref "U80") (pin "1") (pinfunction "VSS_1") (pintype "passive"))
      (node (ref "U81") (pin "1") (pinfunction "VSS_1") (pintype "passive"))
      (node (ref "U82") (pin "1") (pinfunction "VSS_1") (pintype "passive"))
      (node (ref "U83") (pin "1") (pinfunction "VSS_1") (pintype "passive"))
      (node (ref "U84") (pin "1") (pinfunction "VSS_1") (pintype "passive"))
      (node (ref "U85") (pin "1") (pinfunction "VSS_1") (pintype "passive"))
      (node (ref "U86") (pin "1") (pinfunction "VSS_1") (pintype "passive"))
      (node (ref "U87") (pin "1") (pinfunction "VSS_1") (pintype "passive"))
      (node (ref "U88") (pin "1") (pinfunction "VSS_1") (pintype "passive"))
      (node (ref "U89") (pin "1") (pinfunction "VSS_1") (pintype "passive"))
    )
    (net (code "6") (name "Net-(U2-DIN)") (class "Default")
      (node (ref "P3") (pin "2") (pinfunction "2_2") (pintype "passive"))
      (node (ref "U2") (pin "2") (pinfunction "DIN_2") (pintype "passive"))
    )
    (net (code "7") (name "Net-(U2-DOUT)") (class "Default")
      (node (ref "U2") (pin "4") (pinfunction "DOUT_4") (pintype "passive"))
      (node (ref "U3") (pin "2") (pinfunction "DIN_2") (pintype "passive"))
    )
    (net (code "8") (name "Net-(U3-DOUT)") (class "Default")
      (node (ref "U3") (pin "4") (pinfunction "DOUT_4") (pintype "passive"))
      (node (ref "U4") (pin "2") (pinfunction "DIN_2") (pintype "passive"))
    )
    (net (code "9") (name "Net-(U4-DOUT)") (class "Default")
      (node (ref "U4") (pin "4") (pinfunction "DOUT_4") (pintype "passive"))
      (node (ref "U5") (pin "2") (pinfunction "DIN_2") (pintype "passive"))
    )
    (net (code "10") (name "Net-(U5-DOUT)") (class "Default")
      (node (ref "P1") (pin "2") (pinfunction "2_2") (pintype "passive"))
      (node (ref "U5") (pin "4") (pinfunction "DOUT_4") (pintype "passive"))
    )
    (net (code "11") (name "Net-(U7-DIN)") (class "Default")
      (node (ref "P5") (pin "2") (pinfunction "2_2") (pintype "passive"))
      (node (ref "U7") (pin "2") (pinfunction "DIN_2") (pintype "passive"))
    )
    (net (code "12") (name "Net-(U7-DOUT)") (class "Default")
      (node (ref "U7") (pin "4") (pinfunction "DOUT_4") (pintype "passive"))
      (node (ref "U8") (pin "2") (pinfunction "DIN_2") (pintype "passive"))
    )
    (net (code "13") (name "Net-(U8-DOUT)") (class "Default")
      (node (ref "U8") (pin "4") (pinfunction "DOUT_4") (pintype "passive"))
      (node (ref "U9") (pin "2") (pinfunction "DIN_2") (pintype "passive"))
    )
    (net (code "14") (name "Net-(U10-DIN)") (class "Default")
      (node (ref "U10") (pin "2") (pinfunction "DIN_2") (pintype "passive"))
      (node (ref "U9") (pin "4") (pinfunction "DOUT_4") (pintype "passive"))
    )
    (net (code "15") (name "Net-(U10-DOUT)") (class "Default")
      (node (ref "U10") (pin "4") (pinfunction "DOUT_4") (pintype "passive"))
      (node (ref "U11") (pin "2") (pinfunction "DIN_2") (pintype "passive"))
    )
    (net (code "16") (name "Net-(U11-DOUT)") (class "Default")
      (node (ref "U11") (pin "4") (pinfunction "DOUT_4") (pintype "passive"))
      (node (ref "U12") (pin "2") (pinfunction "DIN_2") (pintype "passive"))
    )
    (net (code "17") (name "Net-(U12-DOUT)") (class "Default")
      (node (ref "U12") (pin "4") (pinfunction "DOUT_4") (pintype "passive"))
      (node (ref "U13") (pin "2") (pinfunction "DIN_2") (pintype "passive"))
    )
    (net (code "18") (name "Net-(U13-DOUT)") (class "Default")
      (node (ref "U13") (pin "4") (pinfunction "DOUT_4") (pintype "passive"))
      (node (ref "U14") (pin "2") (pinfunction "DIN_2") (pintype "passive"))
    )
    (net (code "19") (name "Net-(U14-DOUT)") (class "Default")
      (node (ref "P6") (pin "2") (pinfunction "2_2") (pintype "passive"))
      (node (ref "U14") (pin "4") (pinfunction "DOUT_4") (pintype "passive"))
    )
    (net (code "20") (name "Net-(U16-DIN)") (class "Default")
      (node (ref "P8") (pin "2") (pinfunction "2_2") (pintype "passive"))
      (node (ref "U16") (pin "2") (pinfunction "DIN_2") (pintype "passive"))
    )
    (net (code "21") (name "Net-(U16-DOUT)") (class "Default")
      (node (ref "U16") (pin "4") (pinfunction "DOUT_4") (pintype "passive"))
      (node (ref "U17") (pin "2") (pinfunction "DIN_2") (pintype "passive"))
    )
    (net (code "22") (name "Net-(U17-DOUT)") (class "Default")
      (node (ref "U17") (pin "4") (pinfunction "DOUT_4") (pintype "passive"))
      (node (ref "U18") (pin "2") (pinfunction "DIN_2") (pintype "passive"))
    )
    (net (code "23") (name "Net-(U18-DOUT)") (class "Default")
      (node (ref "U18") (pin "4") (pinfunction "DOUT_4") (pintype "passive"))
      (node (ref "U19") (pin "2") (pinfunction "DIN_2") (pintype "passive"))
    )
    (net (code "24") (name "Net-(U19-DOUT)") (class "Default")
      (node (ref "U19") (pin "4") (pinfunction "DOUT_4") (pintype "passive"))
      (node (ref "U20") (pin "2") (pinfunction "DIN_2") (pintype "passive"))
    )
    (net (code "25") (name "Net-(U20-DOUT)") (class "Default")
      (node (ref "U20") (pin "4") (pinfunction "DOUT_4") (pintype "passive"))
      (node (ref "U21") (pin "2") (pinfunction "DIN_2") (pintype "passive"))
    )
    (net (code "26") (name "Net-(U21-DOUT)") (class "Default")
      (node (ref "U21") (pin "4") (pinfunction "DOUT_4") (pintype "passive"))
      (node (ref "U22") (pin "2") (pinfunction "DIN_2") (pintype "passive"))
    )
    (net (code "27") (name "Net-(U22-DOUT)") (class "Default")
      (node (ref "U22") (pin "4") (pinfunction "DOUT_4") (pintype "passive"))
      (node (ref "U23") (pin "2") (pinfunction "DIN_2") (pintype "passive"))
    )
    (net (code "28") (name "Net-(U23-DOUT)") (class "Default")
      (node (ref "U23") (pin "4") (pinfunction "DOUT_4") (pintype "passive"))
      (node (ref "U24") (pin "2") (pinfunction "DIN_2") (pintype "passive"))
    )
    (net (code "29") (name "Net-(U24-DOUT)") (class "Default")
      (node (ref "U24") (pin "4") (pinfunction "DOUT_4") (pintype "passive"))
      (node (ref "U25") (pin "2") (pinfunction "DIN_2") (pintype "passive"))
    )
    (net (code "30") (name "Net-(U25-DOUT)") (class "Default")
      (node (ref "U25") (pin "4") (pinfunction "DOUT_4") (pintype "passive"))
      (node (ref "U26") (pin "2") (pinfunction "DIN_2") (pintype "passive"))
    )
    (net (code "31") (name "Net-(U26-DOUT)") (class "Default")
      (node (ref "U26") (pin "4") (pinfunction "DOUT_4") (pintype "passive"))
      (node (ref "U27") (pin "2") (pinfunction "DIN_2") (pintype "passive"))
    )
    (net (code "32") (name "Net-(U27-DOUT)") (class "Default")
      (node (ref "U27") (pin "4") (pinfunction "DOUT_4") (pintype "passive"))
      (node (ref "U28") (pin "2") (pinfunction "DIN_2") (pintype "passive"))
    )
    (net (code "33") (name "Net-(U28-DOUT)") (class "Default")
      (node (ref "U28") (pin "4") (pinfunction "DOUT_4") (pintype "passive"))
      (node (ref "U29") (pin "2") (pinfunction "DIN_2") (pintype "passive"))
    )
    (net (code "34") (name "Net-(U29-DOUT)") (class "Default")
      (node (ref "U29") (pin "4") (pinfunction "DOUT_4") (pintype "passive"))
      (node (ref "U30") (pin "2") (pinfunction "DIN_2") (pintype "passive"))
    )
    (net (code "35") (name "Net-(U30-DOUT)") (class "Default")
      (node (ref "U30") (pin "4") (pinfunction "DOUT_4") (pintype "passive"))
      (node (ref "U31") (pin "2") (pinfunction "DIN_2") (pintype "passive"))
    )
    (net (code "36") (name "Net-(U31-DOUT)") (class "Default")
      (node (ref "P9") (pin "2") (pinfunction "2_2") (pintype "passive"))
      (node (ref "U31") (pin "4") (pinfunction "DOUT_4") (pintype "passive"))
    )
    (net (code "37") (name "Net-(U33-DIN)") (class "Default")
      (node (ref "P11") (pin "2") (pinfunction "2_2") (pintype "passive"))
      (node (ref "U33") (pin "2") (pinfunction "DIN_2") (pintype "passive"))
    )
    (net (code "38") (name "Net-(U33-DOUT)") (class "Default")
      (node (ref "U33") (pin "4") (pinfunction "DOUT_4") (pintype "passive"))
      (node (ref "U34") (pin "2") (pinfunction "DIN_2") (pintype "passive"))
    )
    (net (code "39") (name "Net-(U34-DOUT)") (class "Default")
      (node (ref "U34") (pin "4") (pinfunction "DOUT_4") (pintype "passive"))
      (node (ref "U35") (pin "2") (pinfunction "DIN_2") (pintype "passive"))
    )
    (net (code "40") (name "Net-(U35-DOUT)") (class "Default")
      (node (ref "U35") (pin "4") (pinfunction "DOUT_4") (pintype "passive"))
      (node (ref "U36") (pin "2") (pinfunction "DIN_2") (pintype "passive"))
    )
    (net (code "41") (name "Net-(U36-DOUT)") (class "Default")
      (node (ref "U36") (pin "4") (pinfunction "DOUT_4") (pintype "passive"))
      (node (ref "U37") (pin "2") (pinfunction "DIN_2") (pintype "passive"))
    )
    (net (code "42") (name "Net-(U37-DOUT)") (class "Default")
      (node (ref "U37") (pin "4") (pinfunction "DOUT_4") (pintype "passive"))
      (node (ref "U38") (pin "2") (pinfunction "DIN_2") (pintype "passive"))
    )
    (net (code "43") (name "Net-(U38-DOUT)") (class "Default")
      (node (ref "U38") (pin "4") (pinfunction "DOUT_4") (pintype "passive"))
      (node (ref "U39") (pin "2") (pinfunction "DIN_2") (pintype "passive"))
    )
    (net (code "44") (name "Net-(U39-DOUT)") (class "Default")
      (node (ref "U39") (pin "4") (pinfunction "DOUT_4") (pintype "passive"))
      (node (ref "U40") (pin "2") (pinfunction "DIN_2") (pintype "passive"))
    )
    (net (code "45") (name "Net-(U40-DOUT)") (class "Default")
      (node (ref "U40") (pin "4") (pinfunction "DOUT_4") (pintype "passive"))
      (node (ref "U41") (pin "2") (pinfunction "DIN_2") (pintype "passive"))
    )
    (net (code "46") (name "Net-(U41-DOUT)") (class "Default")
      (node (ref "U41") (pin "4") (pinfunction "DOUT_4") (pintype "passive"))
      (node (ref "U42") (pin "2") (pinfunction "DIN_2") (pintype "passive"))
    )
    (net (code "47") (name "Net-(U42-DOUT)") (class "Default")
      (node (ref "U42") (pin "4") (pinfunction "DOUT_4") (pintype "passive"))
      (node (ref "U43") (pin "2") (pinfunction "DIN_2") (pintype "passive"))
    )
    (net (code "48") (name "Net-(U43-DOUT)") (class "Default")
      (node (ref "U43") (pin "4") (pinfunction "DOUT_4") (pintype "passive"))
      (node (ref "U44") (pin "2") (pinfunction "DIN_2") (pintype "passive"))
    )
    (net (code "49") (name "Net-(U44-DOUT)") (class "Default")
      (node (ref "U44") (pin "4") (pinfunction "DOUT_4") (pintype "passive"))
      (node (ref "U45") (pin "2") (pinfunction "DIN_2") (pintype "passive"))
    )
    (net (code "50") (name "Net-(U45-DOUT)") (class "Default")
      (node (ref "U45") (pin "4") (pinfunction "DOUT_4") (pintype "passive"))
      (node (ref "U46") (pin "2") (pinfunction "DIN_2") (pintype "passive"))
    )
    (net (code "51") (name "Net-(U46-DOUT)") (class "Default")
      (node (ref "U46") (pin "4") (pinfunction "DOUT_4") (pintype "passive"))
      (node (ref "U47") (pin "2") (pinfunction "DIN_2") (pintype "passive"))
    )
    (net (code "52") (name "Net-(U47-DOUT)") (class "Default")
      (node (ref "U47") (pin "4") (pinfunction "DOUT_4") (pintype "passive"))
      (node (ref "U48") (pin "2") (pinfunction "DIN_2") (pintype "passive"))
    )
    (net (code "53") (name "Net-(U48-DOUT)") (class "Default")
      (node (ref "U48") (pin "4") (pinfunction "DOUT_4") (pintype "passive"))
      (node (ref "U49") (pin "2") (pinfunction "DIN_2") (pintype "passive"))
    )
    (net (code "54") (name "Net-(U49-DOUT)") (class "Default")
      (node (ref "U49") (pin "4") (pinfunction "DOUT_4") (pintype "passive"))
      (node (ref "U50") (pin "2") (pinfunction "DIN_2") (pintype "passive"))
    )
    (net (code "55") (name "Net-(U50-DOUT)") (class "Default")
      (node (ref "U50") (pin "4") (pinfunction "DOUT_4") (pintype "passive"))
      (node (ref "U51") (pin "2") (pinfunction "DIN_2") (pintype "passive"))
    )
    (net (code "56") (name "Net-(U51-DOUT)") (class "Default")
      (node (ref "U51") (pin "4") (pinfunction "DOUT_4") (pintype "passive"))
      (node (ref "U52") (pin "2") (pinfunction "DIN_2") (pintype "passive"))
    )
    (net (code "57") (name "Net-(U52-DOUT)") (class "Default")
      (node (ref "U52") (pin "4") (pinfunction "DOUT_4") (pintype "passive"))
      (node (ref "U53") (pin "2") (pinfunction "DIN_2") (pintype "passive"))
    )
    (net (code "58") (name "Net-(U53-DOUT)") (class "Default")
      (node (ref "U53") (pin "4") (pinfunction "DOUT_4") (pintype "passive"))
      (node (ref "U54") (pin "2") (pinfunction "DIN_2") (pintype "passive"))
    )
    (net (code "59") (name "Net-(U54-DOUT)") (class "Default")
      (node (ref "U54") (pin "4") (pinfunction "DOUT_4") (pintype "passive"))
      (node (ref "U55") (pin "2") (pinfunction "DIN_2") (pintype "passive"))
    )
    (net (code "60") (name "Net-(U55-DOUT)") (class "Default")
      (node (ref "U55") (pin "4") (pinfunction "DOUT_4") (pintype "passive"))
      (node (ref "U56") (pin "2") (pinfunction "DIN_2") (pintype "passive"))
    )
    (net (code "61") (name "Net-(U56-DOUT)") (class "Default")
      (node (ref "P12") (pin "2") (pinfunction "2_2") (pintype "passive"))
      (node (ref "U56") (pin "4") (pinfunction "DOUT_4") (pintype "passive"))
    )
    (net (code "62") (name "Net-(U58-DIN)") (class "Default")
      (node (ref "P14") (pin "2") (pinfunction "2_2") (pintype "passive"))
      (node (ref "U58") (pin "2") (pinfunction "DIN_2") (pintype "passive"))
    )
    (net (code "63") (name "Net-(U58-DOUT)") (class "Default")
      (node (ref "U58") (pin "4") (pinfunction "DOUT_4") (pintype "passive"))
      (node (ref "U59") (pin "2") (pinfunction "DIN_2") (pintype "passive"))
    )
    (net (code "64") (name "Net-(U59-DOUT)") (class "Default")
      (node (ref "U59") (pin "4") (pinfunction "DOUT_4") (pintype "passive"))
      (node (ref "U60") (pin "2") (pinfunction "DIN_2") (pintype "passive"))
    )
    (net (code "65") (name "Net-(U60-DOUT)") (class "Default")
      (node (ref "U60") (pin "4") (pinfunction "DOUT_4") (pintype "passive"))
      (node (ref "U61") (pin "2") (pinfunction "DIN_2") (pintype "passive"))
    )
    (net (code "66") (name "Net-(U61-DOUT)") (class "Default")
      (node (ref "U61") (pin "4") (pinfunction "DOUT_4") (pintype "passive"))
      (node (ref "U62") (pin "2") (pinfunction "DIN_2") (pintype "passive"))
    )
    (net (code "67") (name "Net-(U62-DOUT)") (class "Default")
      (node (ref "U62") (pin "4") (pinfunction "DOUT_4") (pintype "passive"))
      (node (ref "U63") (pin "2") (pinfunction "DIN_2") (pintype "passive"))
    )
    (net (code "68") (name "Net-(U63-DOUT)") (class "Default")
      (node (ref "U63") (pin "4") (pinfunction "DOUT_4") (pintype "passive"))
      (node (ref "U64") (pin "2") (pinfunction "DIN_2") (pintype "passive"))
    )
    (net (code "69") (name "Net-(U64-DOUT)") (class "Default")
      (node (ref "U64") (pin "4") (pinfunction "DOUT_4") (pintype "passive"))
      (node (ref "U65") (pin "2") (pinfunction "DIN_2") (pintype "passive"))
    )
    (net (code "70") (name "Net-(U65-DOUT)") (class "Default")
      (node (ref "U65") (pin "4") (pinfunction "DOUT_4") (pintype "passive"))
      (node (ref "U66") (pin "2") (pinfunction "DIN_2") (pintype "passive"))
    )
    (net (code "71") (name "Net-(U66-DOUT)") (class "Default")
      (node (ref "U66") (pin "4") (pinfunction "DOUT_4") (pintype "passive"))
      (node (ref "U67") (pin "2") (pinfunction "DIN_2") (pintype "passive"))
    )
    (net (code "72") (name "Net-(U67-DOUT)") (class "Default")
      (node (ref "U67") (pin "4") (pinfunction "DOUT_4") (pintype "passive"))
      (node (ref "U68") (pin "2") (pinfunction "DIN_2") (pintype "passive"))
    )
    (net (code "73") (name "Net-(U68-DOUT)") (class "Default")
      (node (ref "U68") (pin "4") (pinfunction "DOUT_4") (pintype "passive"))
      (node (ref "U69") (pin "2") (pinfunction "DIN_2") (pintype "passive"))
    )
    (net (code "74") (name "Net-(U69-DOUT)") (class "Default")
      (node (ref "U69") (pin "4") (pinfunction "DOUT_4") (pintype "passive"))
      (node (ref "U70") (pin "2") (pinfunction "DIN_2") (pintype "passive"))
    )
    (net (code "75") (name "Net-(U70-DOUT)") (class "Default")
      (node (ref "U70") (pin "4") (pinfunction "DOUT_4") (pintype "passive"))
      (node (ref "U71") (pin "2") (pinfunction "DIN_2") (pintype "passive"))
    )
    (net (code "76") (name "Net-(U71-DOUT)") (class "Default")
      (node (ref "U71") (pin "4") (pinfunction "DOUT_4") (pintype "passive"))
      (node (ref "U72") (pin "2") (pinfunction "DIN_2") (pintype "passive"))
    )
    (net (code "77") (name "Net-(U72-DOUT)") (class "Default")
      (node (ref "U72") (pin "4") (pinfunction "DOUT_4") (pintype "passive"))
      (node (ref "U73") (pin "2") (pinfunction "DIN_2") (pintype "passive"))
    )
    (net (code "78") (name "Net-(U73-DOUT)") (class "Default")
      (node (ref "U73") (pin "4") (pinfunction "DOUT_4") (pintype "passive"))
      (node (ref "U89") (pin "2") (pinfunction "DIN_2") (pintype "passive"))
    )
    (net (code "79") (name "Net-(U74-DIN)") (class "Default")
      (node (ref "U74") (pin "2") (pinfunction "DIN_2") (pintype "passive"))
      (node (ref "U75") (pin "4") (pinfunction "DOUT_4") (pintype "passive"))
    )
    (net (code "80") (name "Net-(U74-DOUT)") (class "Default")
      (node (ref "P15") (pin "2") (pinfunction "2_2") (pintype "passive"))
      (node (ref "U74") (pin "4") (pinfunction "DOUT_4") (pintype "passive"))
    )
    (net (code "81") (name "Net-(U75-DIN)") (class "Default")
      (node (ref "U75") (pin "2") (pinfunction "DIN_2") (pintype "passive"))
      (node (ref "U76") (pin "4") (pinfunction "DOUT_4") (pintype "passive"))
    )
    (net (code "82") (name "Net-(U76-DIN)") (class "Default")
      (node (ref "U76") (pin "2") (pinfunction "DIN_2") (pintype "passive"))
      (node (ref "U77") (pin "4") (pinfunction "DOUT_4") (pintype "passive"))
    )
    (net (code "83") (name "Net-(U77-DIN)") (class "Default")
      (node (ref "U77") (pin "2") (pinfunction "DIN_2") (pintype "passive"))
      (node (ref "U78") (pin "4") (pinfunction "DOUT_4") (pintype "passive"))
    )
    (net (code "84") (name "Net-(U78-DIN)") (class "Default")
      (node (ref "U78") (pin "2") (pinfunction "DIN_2") (pintype "passive"))
      (node (ref "U79") (pin "4") (pinfunction "DOUT_4") (pintype "passive"))
    )
    (net (code "85") (name "Net-(U79-DIN)") (class "Default")
      (node (ref "U79") (pin "2") (pinfunction "DIN_2") (pintype "passive"))
      (node (ref "U80") (pin "4") (pinfunction "DOUT_4") (pintype "passive"))
    )
    (net (code "86") (name "Net-(U80-DIN)") (class "Default")
      (node (ref "U80") (pin "2") (pinfunction "DIN_2") (pintype "passive"))
      (node (ref "U81") (pin "4") (pinfunction "DOUT_4") (pintype "passive"))
    )
    (net (code "87") (name "Net-(U81-DIN)") (class "Default")
      (node (ref "U81") (pin "2") (pinfunction "DIN_2") (pintype "passive"))
      (node (ref "U82") (pin "4") (pinfunction "DOUT_4") (pintype "passive"))
    )
    (net (code "88") (name "Net-(U82-DIN)") (class "Default")
      (node (ref "U82") (pin "2") (pinfunction "DIN_2") (pintype "passive"))
      (node (ref "U83") (pin "4") (pinfunction "DOUT_4") (pintype "passive"))
    )
    (net (code "89") (name "Net-(U83-DIN)") (class "Default")
      (node (ref "U83") (pin "2") (pinfunction "DIN_2") (pintype "passive"))
      (node (ref "U84") (pin "4") (pinfunction "DOUT_4") (pintype "passive"))
    )
    (net (code "90") (name "Net-(U84-DIN)") (class "Default")
      (node (ref "U84") (pin "2") (pinfunction "DIN_2") (pintype "passive"))
      (node (ref "U85") (pin "4") (pinfunction "DOUT_4") (pintype "passive"))
    )
    (net (code "91") (name "Net-(U85-DIN)") (class "Default")
      (node (ref "U85") (pin "2") (pinfunction "DIN_2") (pintype "passive"))
      (node (ref "U86") (pin "4") (pinfunction "DOUT_4") (pintype "passive"))
    )
    (net (code "92") (name "Net-(U86-DIN)") (class "Default")
      (node (ref "U86") (pin "2") (pinfunction "DIN_2") (pintype "passive"))
      (node (ref "U87") (pin "4") (pinfunction "DOUT_4") (pintype "passive"))
    )
    (net (code "93") (name "Net-(U87-DIN)") (class "Default")
      (node (ref "U87") (pin "2") (pinfunction "DIN_2") (pintype "passive"))
      (node (ref "U88") (pin "4") (pinfunction "DOUT_4") (pintype "passive"))
    )
    (net (code "94") (name "Net-(U88-DIN)") (class "Default")
      (node (ref "U88") (pin "2") (pinfunction "DIN_2") (pintype "passive"))
      (node (ref "U89") (pin "4") (pinfunction "DOUT_4") (pintype "passive"))
    )
    (net (code "95") (name "VCC") (class "Default")
      (node (ref "C1") (pin "2") (pinfunction "2_2") (pintype "passive"))
      (node (ref "C2") (pin "2") (pinfunction "2_2") (pintype "passive"))
      (node (ref "C3") (pin "2") (pinfunction "2_2") (pintype "passive"))
      (node (ref "C4") (pin "2") (pinfunction "2_2") (pintype "passive"))
      (node (ref "P1") (pin "1") (pinfunction "1_1") (pintype "passive"))
      (node (ref "P3") (pin "1") (pinfunction "1_1") (pintype "passive"))
      (node (ref "U2") (pin "3") (pinfunction "VDD_3") (pintype "passive"))
      (node (ref "U3") (pin "3") (pinfunction "VDD_3") (pintype "passive"))
      (node (ref "U4") (pin "3") (pinfunction "VDD_3") (pintype "passive"))
      (node (ref "U5") (pin "3") (pinfunction "VDD_3") (pintype "passive"))
    )
    (net (code "96") (name "VCC1") (class "Default")
      (node (ref "C10") (pin "2") (pinfunction "2_2") (pintype "passive"))
      (node (ref "C11") (pin "2") (pinfunction "2_2") (pintype "passive"))
      (node (ref "C12") (pin "2") (pinfunction "2_2") (pintype "passive"))
      (node (ref "C5") (pin "2") (pinfunction "2_2") (pintype "passive"))
      (node (ref "C6") (pin "2") (pinfunction "2_2") (pintype "passive"))
      (node (ref "C7") (pin "2") (pinfunction "2_2") (pintype "passive"))
      (node (ref "C8") (pin "2") (pinfunction "2_2") (pintype "passive"))
      (node (ref "C9") (pin "2") (pinfunction "2_2") (pintype "passive"))
      (node (ref "P5") (pin "3") (pinfunction "3_3") (pintype "passive"))
      (node (ref "P6") (pin "3") (pinfunction "3_3") (pintype "passive"))
      (node (ref "U10") (pin "3") (pinfunction "VDD_3") (pintype "passive"))
      (node (ref "U11") (pin "3") (pinfunction "VDD_3") (pintype "passive"))
      (node (ref "U12") (pin "3") (pinfunction "VDD_3") (pintype "passive"))
      (node (ref "U13") (pin "3") (pinfunction "VDD_3") (pintype "passive"))
      (node (ref "U14") (pin "3") (pinfunction "VDD_3") (pintype "passive"))
      (node (ref "U7") (pin "3") (pinfunction "VDD_3") (pintype "passive"))
      (node (ref "U8") (pin "3") (pinfunction "VDD_3") (pintype "passive"))
      (node (ref "U9") (pin "3") (pinfunction "VDD_3") (pintype "passive"))
    )
    (net (code "97") (name "VCC2") (class "Default")
      (node (ref "C13") (pin "2") (pinfunction "2_2") (pintype "passive"))
      (node (ref "C14") (pin "2") (pinfunction "2_2") (pintype "passive"))
      (node (ref "C15") (pin "2") (pinfunction "2_2") (pintype "passive"))
      (node (ref "C16") (pin "2") (pinfunction "2_2") (pintype "passive"))
      (node (ref "C17") (pin "2") (pinfunction "2_2") (pintype "passive"))
      (node (ref "C18") (pin "2") (pinfunction "2_2") (pintype "passive"))
      (node (ref "C19") (pin "2") (pinfunction "2_2") (pintype "passive"))
      (node (ref "C20") (pin "2") (pinfunction "2_2") (pintype "passive"))
      (node (ref "C21") (pin "2") (pinfunction "2_2") (pintype "passive"))
      (node (ref "C22") (pin "2") (pinfunction "2_2") (pintype "passive"))
      (node (ref "C23") (pin "2") (pinfunction "2_2") (pintype "passive"))
      (node (ref "C24") (pin "2") (pinfunction "2_2") (pintype "passive"))
      (node (ref "C25") (pin "2") (pinfunction "2_2") (pintype "passive"))
      (node (ref "C26") (pin "2") (pinfunction "2_2") (pintype "passive"))
      (node (ref "C27") (pin "2") (pinfunction "2_2") (pintype "passive"))
      (node (ref "C28") (pin "2") (pinfunction "2_2") (pintype "passive"))
      (node (ref "P8") (pin "3") (pinfunction "3_3") (pintype "passive"))
      (node (ref "P9") (pin "3") (pinfunction "3_3") (pintype "passive"))
      (node (ref "U16") (pin "3") (pinfunction "VDD_3") (pintype "passive"))
      (node (ref "U17") (pin "3") (pinfunction "VDD_3") (pintype "passive"))
      (node (ref "U18") (pin "3") (pinfunction "VDD_3") (pintype "passive"))
      (node (ref "U19") (pin "3") (pinfunction "VDD_3") (pintype "passive"))
      (node (ref "U20") (pin "3") (pinfunction "VDD_3") (pintype "passive"))
      (node (ref "U21") (pin "3") (pinfunction "VDD_3") (pintype "passive"))
      (node (ref "U22") (pin "3") (pinfunction "VDD_3") (pintype "passive"))
      (node (ref "U23") (pin "3") (pinfunction "VDD_3") (pintype "passive"))
      (node (ref "U24") (pin "3") (pinfunction "VDD_3") (pintype "passive"))
      (node (ref "U25") (pin "3") (pinfunction "VDD_3") (pintype "passive"))
      (node (ref "U26") (pin "3") (pinfunction "VDD_3") (pintype "passive"))
      (node (ref "U27") (pin "3") (pinfunction "VDD_3") (pintype "passive"))
      (node (ref "U28") (pin "3") (pinfunction "VDD_3") (pintype "passive"))
      (node (ref "U29") (pin "3") (pinfunction "VDD_3") (pintype "passive"))
      (node (ref "U30") (pin "3") (pinfunction "VDD_3") (pintype "passive"))
      (node (ref "U31") (pin "3") (pinfunction "VDD_3") (pintype "passive"))
    )
    (net (code "98") (name "VCC3") (class "Default")
      (node (ref "C29") (pin "2") (pinfunction "2_2") (pintype "passive"))
      (node (ref "C30") (pin "2") (pinfunction "2_2") (pintype "passive"))
      (node (ref "C31") (pin "2") (pinfunction "2_2") (pintype "passive"))
      (node (ref "C32") (pin "2") (pinfunction "2_2") (pintype "passive"))
      (node (ref "C33") (pin "2") (pinfunction "2_2") (pintype "passive"))
      (node (ref "C34") (pin "2") (pinfunction "2_2") (pintype "passive"))
      (node (ref "C35") (pin "2") (pinfunction "2_2") (pintype "passive"))
      (node (ref "C36") (pin "2") (pinfunction "2_2") (pintype "passive"))
      (node (ref "C37") (pin "2") (pinfunction "2_2") (pintype "passive"))
      (node (ref "C38") (pin "2") (pinfunction "2_2") (pintype "passive"))
      (node (ref "C39") (pin "2") (pinfunction "2_2") (pintype "passive"))
      (node (ref "C40") (pin "2") (pinfunction "2_2") (pintype "passive"))
      (node (ref "C41") (pin "2") (pinfunction "2_2") (pintype "passive"))
      (node (ref "C42") (pin "2") (pinfunction "2_2") (pintype "passive"))
      (node (ref "C43") (pin "2") (pinfunction "2_2") (pintype "passive"))
      (node (ref "C44") (pin "2") (pinfunction "2_2") (pintype "passive"))
      (node (ref "C45") (pin "2") (pinfunction "2_2") (pintype "passive"))
      (node (ref "C46") (pin "2") (pinfunction "2_2") (pintype "passive"))
      (node (ref "C47") (pin "2") (pinfunction "2_2") (pintype "passive"))
      (node (ref "C48") (pin "2") (pinfunction "2_2") (pintype "passive"))
      (node (ref "C49") (pin "2") (pinfunction "2_2") (pintype "passive"))
      (node (ref "C50") (pin "2") (pinfunction "2_2") (pintype "passive"))
      (node (ref "C51") (pin "2") (pinfunction "2_2") (pintype "passive"))
      (node (ref "C52") (pin "2") (pinfunction "2_2") (pintype "passive"))
      (node (ref "P11") (pin "3") (pinfunction "3_3") (pintype "passive"))
      (node (ref "P12") (pin "3") (pinfunction "3_3") (pintype "passive"))
      (node (ref "U33") (pin "3") (pinfunction "VDD_3") (pintype "passive"))
      (node (ref "U34") (pin "3") (pinfunction "VDD_3") (pintype "passive"))
      (node (ref "U35") (pin "3") (pinfunction "VDD_3") (pintype "passive"))
      (node (ref "U36") (pin "3") (pinfunction "VDD_3") (pintype "passive"))
      (node (ref "U37") (pin "3") (pinfunction "VDD_3") (pintype "passive"))
      (node (ref "U38") (pin "3") (pinfunction "VDD_3") (pintype "passive"))
      (node (ref "U39") (pin "3") (pinfunction "VDD_3") (pintype "passive"))
      (node (ref "U40") (pin "3") (pinfunction "VDD_3") (pintype "passive"))
      (node (ref "U41") (pin "3") (pinfunction "VDD_3") (pintype "passive"))
      (node (ref "U42") (pin "3") (pinfunction "VDD_3") (pintype "passive"))
      (node (ref "U43") (pin "3") (pinfunction "VDD_3") (pintype "passive"))
      (node (ref "U44") (pin "3") (pinfunction "VDD_3") (pintype "passive"))
      (node (ref "U45") (pin "3") (pinfunction "VDD_3") (pintype "passive"))
      (node (ref "U46") (pin "3") (pinfunction "VDD_3") (pintype "passive"))
      (node (ref "U47") (pin "3") (pinfunction "VDD_3") (pintype "passive"))
      (node (ref "U48") (pin "3") (pinfunction "VDD_3") (pintype "passive"))
      (node (ref "U49") (pin "3") (pinfunction "VDD_3") (pintype "passive"))
      (node (ref "U50") (pin "3") (pinfunction "VDD_3") (pintype "passive"))
      (node (ref "U51") (pin "3") (pinfunction "VDD_3") (pintype "passive"))
      (node (ref "U52") (pin "3") (pinfunction "VDD_3") (pintype "passive"))
      (node (ref "U53") (pin "3") (pinfunction "VDD_3") (pintype "passive"))
      (node (ref "U54") (pin "3") (pinfunction "VDD_3") (pintype "passive"))
      (node (ref "U55") (pin "3") (pinfunction "VDD_3") (pintype "passive"))
      (node (ref "U56") (pin "3") (pinfunction "VDD_3") (pintype "passive"))
    )
    (net (code "99") (name "VCC4") (class "Default")
      (node (ref "C53") (pin "2") (pinfunction "2_2") (pintype "passive"))
      (node (ref "C54") (pin "2") (pinfunction "2_2") (pintype "passive"))
      (node (ref "C55") (pin "2") (pinfunction "2_2") (pintype "passive"))
      (node (ref "C56") (pin "2") (pinfunction "2_2") (pintype "passive"))
      (node (ref "C57") (pin "2") (pinfunction "2_2") (pintype "passive"))
      (node (ref "C58") (pin "2") (pinfunction "2_2") (pintype "passive"))
      (node (ref "C59") (pin "2") (pinfunction "2_2") (pintype "passive"))
      (node (ref "C60") (pin "2") (pinfunction "2_2") (pintype "passive"))
      (node (ref "C61") (pin "2") (pinfunction "2_2") (pintype "passive"))
      (node (ref "C62") (pin "2") (pinfunction "2_2") (pintype "passive"))
      (node (ref "C63") (pin "2") (pinfunction "2_2") (pintype "passive"))
      (node (ref "C64") (pin "2") (pinfunction "2_2") (pintype "passive"))
      (node (ref "C65") (pin "2") (pinfunction "2_2") (pintype "passive"))
      (node (ref "C66") (pin "2") (pinfunction "2_2") (pintype "passive"))
      (node (ref "C67") (pin "2") (pinfunction "2_2") (pintype "passive"))
      (node (ref "C68") (pin "2") (pinfunction "2_2") (pintype "passive"))
      (node (ref "C69") (pin "2") (pinfunction "2_2") (pintype "passive"))
      (node (ref "C70") (pin "2") (pinfunction "2_2") (pintype "passive"))
      (node (ref "C71") (pin "2") (pinfunction "2_2") (pintype "passive"))
      (node (ref "C72") (pin "2") (pinfunction "2_2") (pintype "passive"))
      (node (ref "C73") (pin "2") (pinfunction "2_2") (pintype "passive"))
      (node (ref "C74") (pin "2") (pinfunction "2_2") (pintype "passive"))
      (node (ref "C75") (pin "2") (pinfunction "2_2") (pintype "passive"))
      (node (ref "C76") (pin "2") (pinfunction "2_2") (pintype "passive"))
      (node (ref "C77") (pin "2") (pinfunction "2_2") (pintype "passive"))
      (node (ref "C78") (pin "2") (pinfunction "2_2") (pintype "passive"))
      (node (ref "C79") (pin "2") (pinfunction "2_2") (pintype "passive"))
      (node (ref "C80") (pin "2") (pinfunction "2_2") (pintype "passive"))
      (node (ref "C81") (pin "2") (pinfunction "2_2") (pintype "passive"))
      (node (ref "C82") (pin "2") (pinfunction "2_2") (pintype "passive"))
      (node (ref "C83") (pin "2") (pinfunction "2_2") (pintype "passive"))
      (node (ref "C84") (pin "2") (pinfunction "2_2") (pintype "passive"))
      (node (ref "P14") (pin "3") (pinfunction "3_3") (pintype "passive"))
      (node (ref "P15") (pin "3") (pinfunction "3_3") (pintype "passive"))
      (node (ref "U58") (pin "3") (pinfunction "VDD_3") (pintype "passive"))
      (node (ref "U59") (pin "3") (pinfunction "VDD_3") (pintype "passive"))
      (node (ref "U60") (pin "3") (pinfunction "VDD_3") (pintype "passive"))
      (node (ref "U61") (pin "3") (pinfunction "VDD_3") (pintype "passive"))
      (node (ref "U62") (pin "3") (pinfunction "VDD_3") (pintype "passive"))
      (node (ref "U63") (pin "3") (pinfunction "VDD_3") (pintype "passive"))
      (node (ref "U64") (pin "3") (pinfunction "VDD_3") (pintype "passive"))
      (node (ref "U65") (pin "3") (pinfunction "VDD_3") (pintype "passive"))
      (node (ref "U66") (pin "3") (pinfunction "VDD_3") (pintype "passive"))
      (node (ref "U67") (pin "3") (pinfunction "VDD_3") (pintype "passive"))
      (node (ref "U68") (pin "3") (pinfunction "VDD_3") (pintype "passive"))
      (node (ref "U69") (pin "3") (pinfunction "VDD_3") (pintype "passive"))
      (node (ref "U70") (pin "3") (pinfunction "VDD_3") (pintype "passive"))
      (node (ref "U71") (pin "3") (pinfunction "VDD_3") (pintype "passive"))
      (node (ref "U72") (pin "3") (pinfunction "VDD_3") (pintype "passive"))
      (node (ref "U73") (pin "3") (pinfunction "VDD_3") (pintype "passive"))
      (node (ref "U74") (pin "3") (pinfunction "VDD_3") (pintype "passive"))
      (node (ref "U75") (pin "3") (pinfunction "VDD_3") (pintype "passive"))
      (node (ref "U76") (pin "3") (pinfunction "VDD_3") (pintype "passive"))
      (node (ref "U77") (pin "3") (pinfunction "VDD_3") (pintype "passive"))
      (node (ref "U78") (pin "3") (pinfunction "VDD_3") (pintype "passive"))
      (node (ref "U79") (pin "3") (pinfunction "VDD_3") (pintype "passive"))
      (node (ref "U80") (pin "3") (pinfunction "VDD_3") (pintype "passive"))
      (node (ref "U81") (pin "3") (pinfunction "VDD_3") (pintype "passive"))
      (node (ref "U82") (pin "3") (pinfunction "VDD_3") (pintype "passive"))
      (node (ref "U83") (pin "3") (pinfunction "VDD_3") (pintype "passive"))
      (node (ref "U84") (pin "3") (pinfunction "VDD_3") (pintype "passive"))
      (node (ref "U85") (pin "3") (pinfunction "VDD_3") (pintype "passive"))
      (node (ref "U86") (pin "3") (pinfunction "VDD_3") (pintype "passive"))
      (node (ref "U87") (pin "3") (pinfunction "VDD_3") (pintype "passive"))
      (node (ref "U88") (pin "3") (pinfunction "VDD_3") (pintype "passive"))
      (node (ref "U89") (pin "3") (pinfunction "VDD_3") (pintype "passive"))
    )
  )
)
